# vldp-hw-rev03.net
KiCad netlist of a schematic drawn in EAGLE
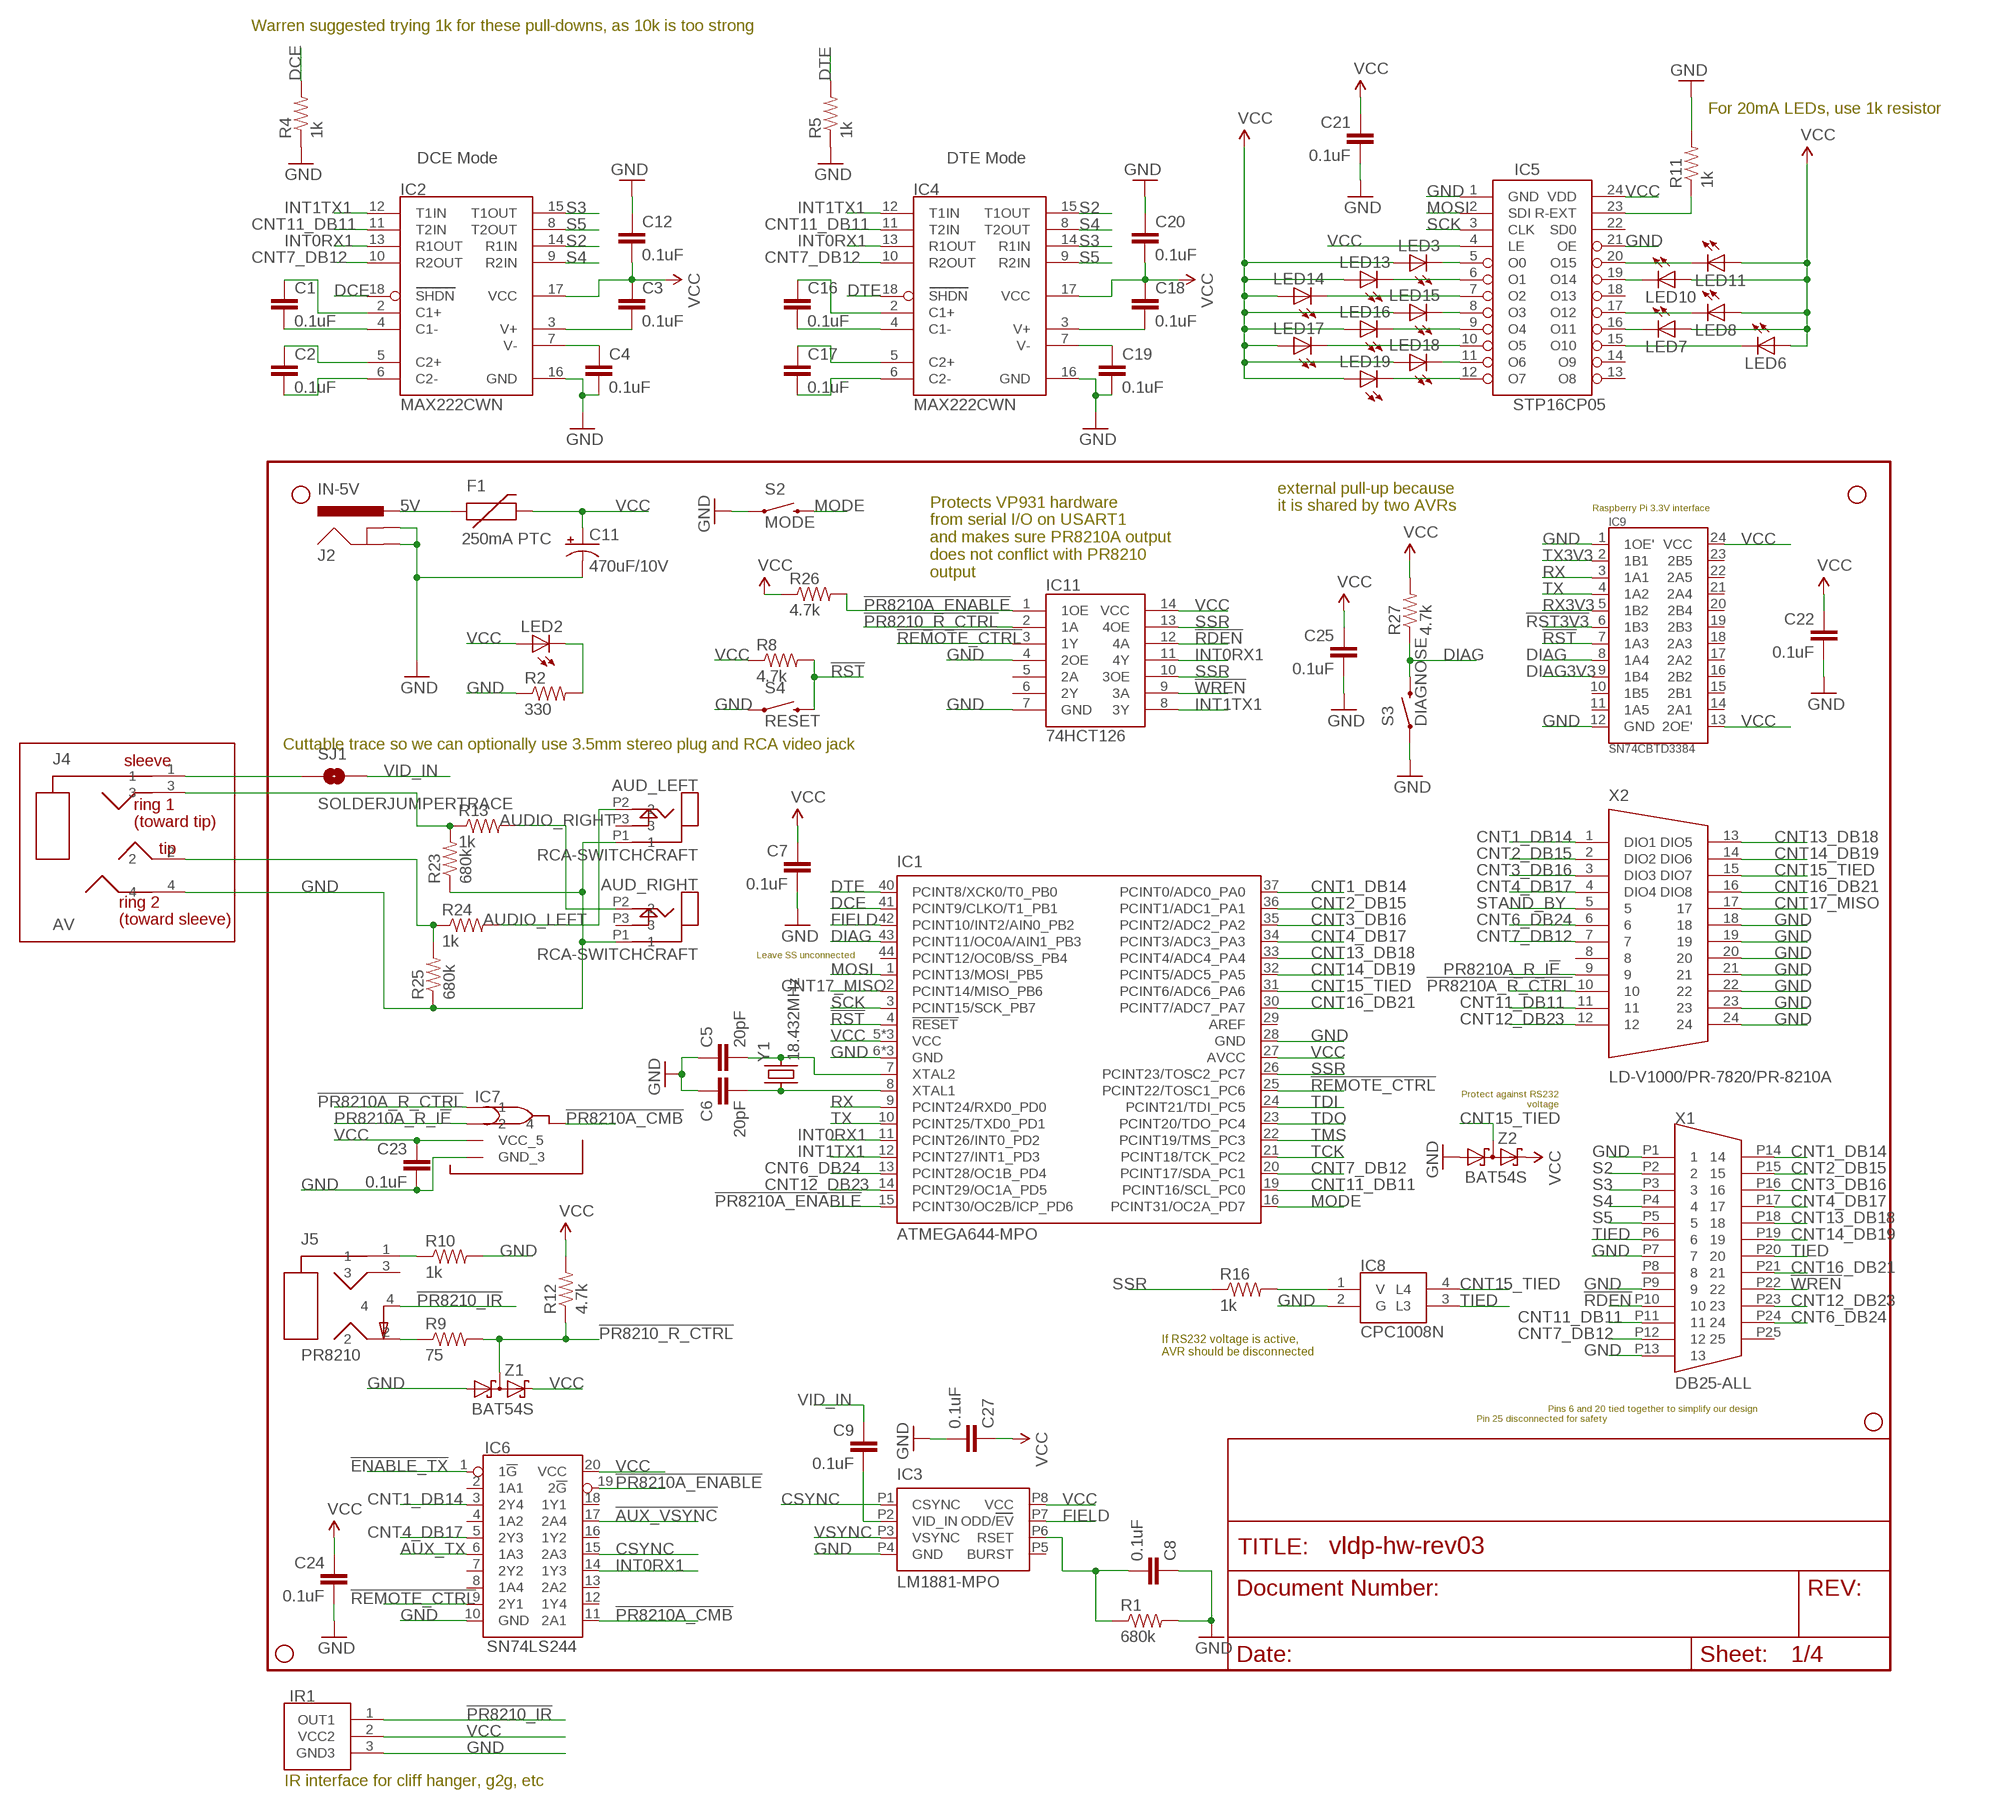
[diagram p0: schematic, sheet 1]
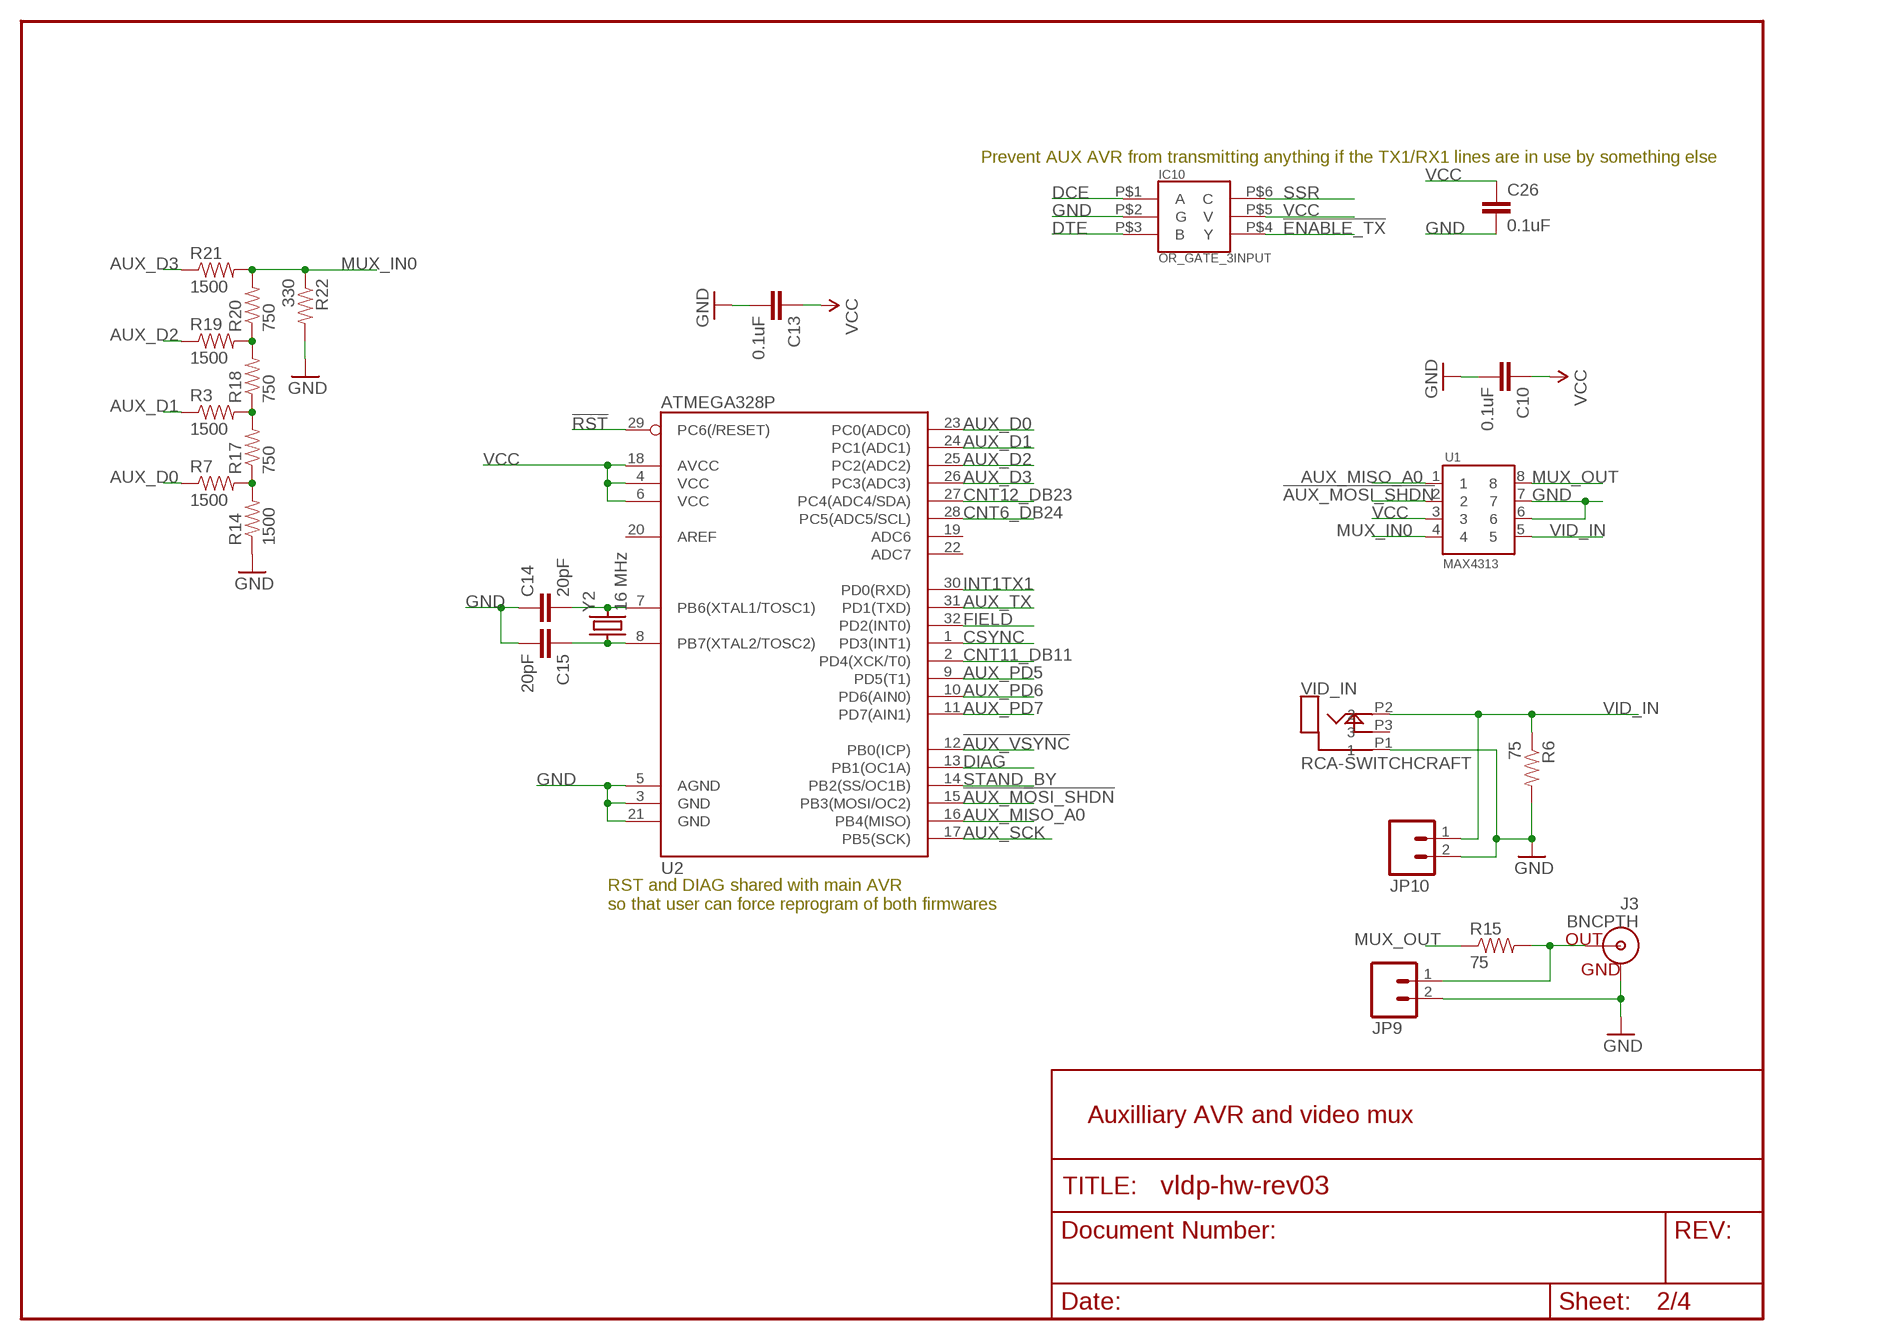
[diagram p1: schematic, sheet 2]
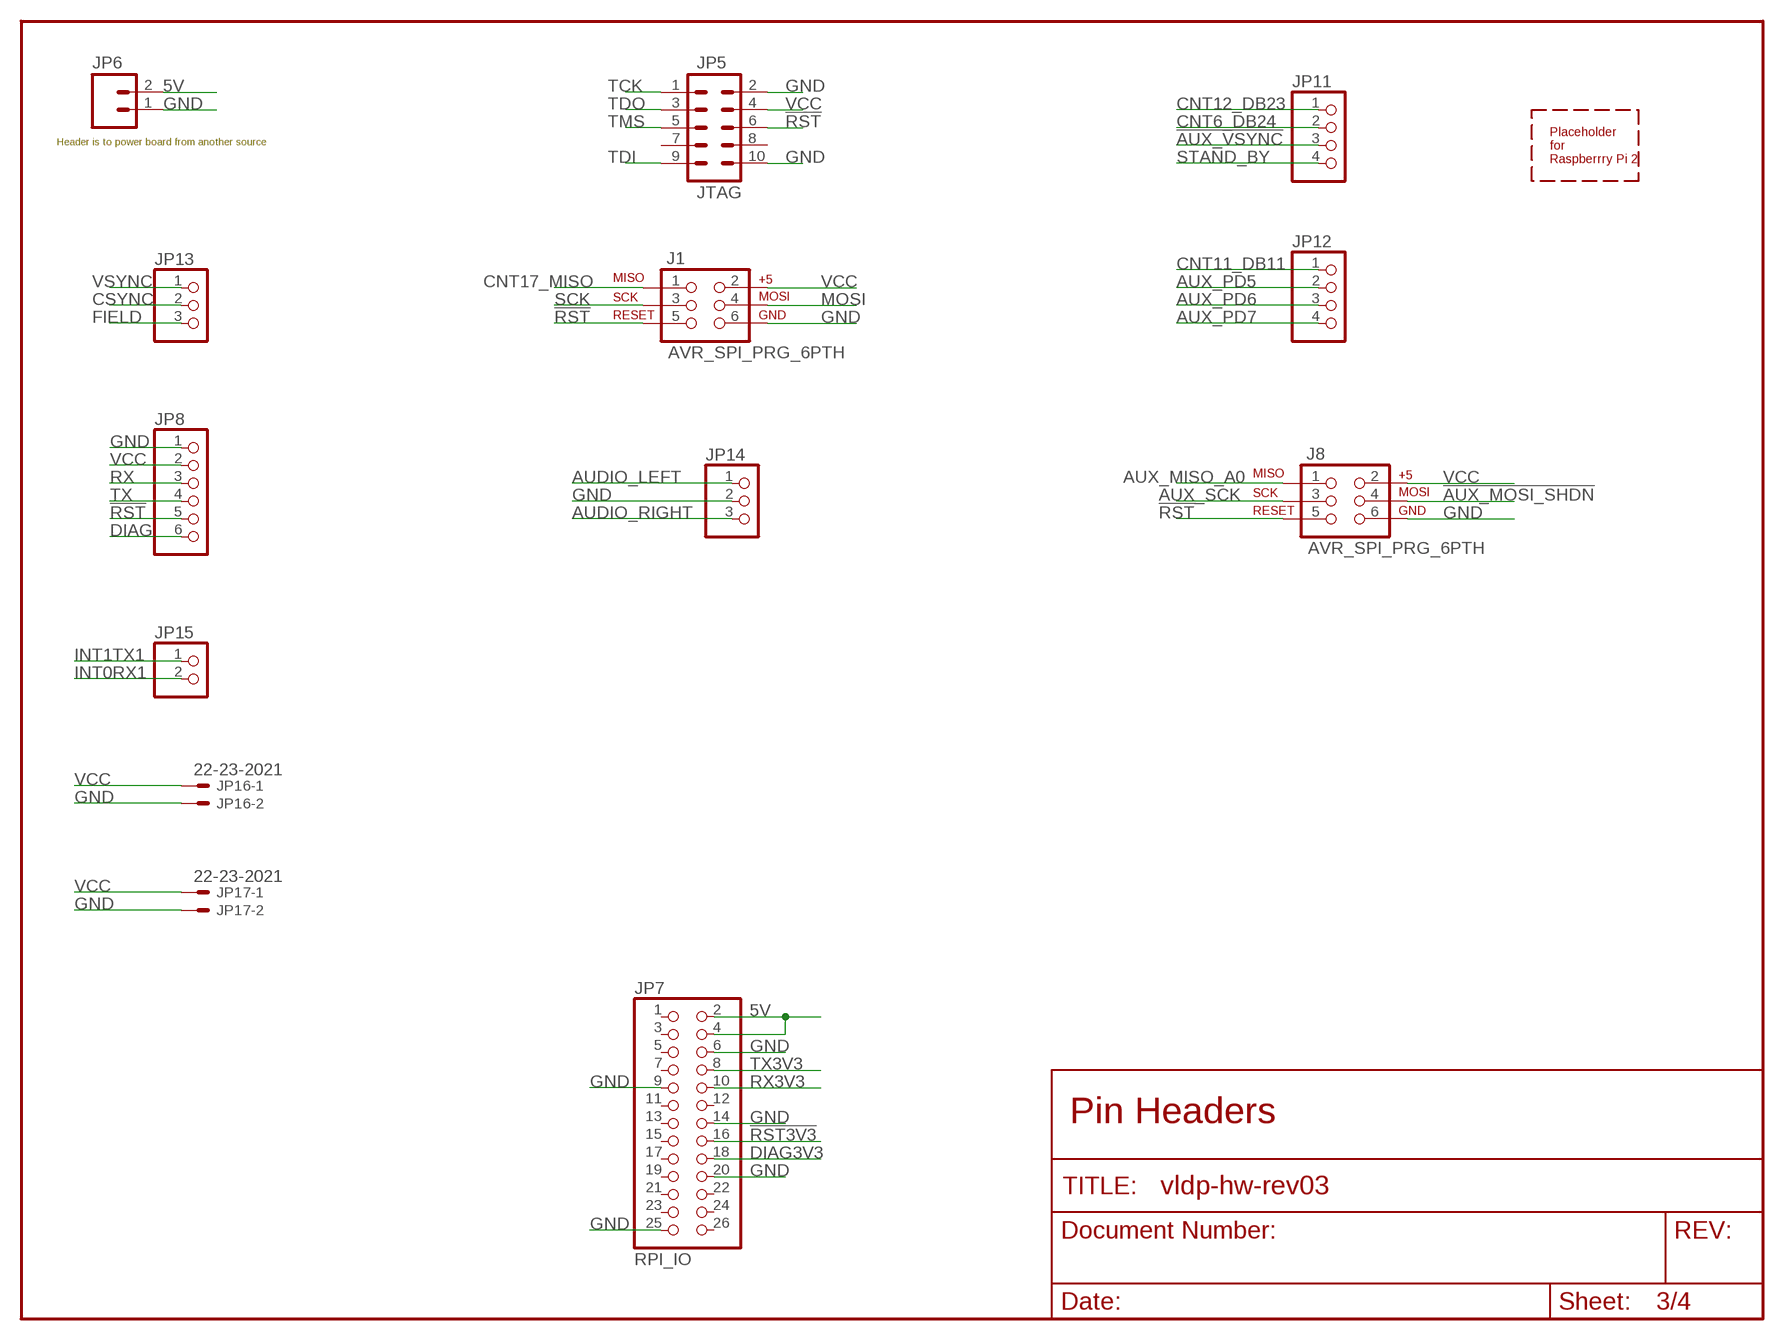
[diagram p2: schematic, sheet 3]

(export (version "E")
  (design (tool "Eeschema 10.0.6"))
  (components
    (comp (ref "J1")
      (value "AVR_SPI_PRG_6PTH")
      (footprint "eagle-import:2X3")
      (libsource (lib "eagle-import") (part "AVR_SPI_PRG_6PTH"))
    )
    (comp (ref "J8")
      (value "AVR_SPI_PRG_6PTH")
      (footprint "eagle-import:2X3")
      (libsource (lib "eagle-import") (part "AVR_SPI_PRG_6PTH"))
    )
    (comp (ref "JP5")
      (value "JTAG")
      (footprint "eagle-import:AVR_ICSP")
      (libsource (lib "eagle-import") (part "M05X2PTH"))
    )
    (comp (ref "JP6")
      (value "M02PTH")
      (footprint "eagle-import:1X02")
      (libsource (lib "eagle-import") (part "M02PTH"))
    )
    (comp (ref "JP7")
      (value "RPI_IO")
      (footprint "eagle-import:2X13")
      (libsource (lib "eagle-import") (part "PINHD-2X13"))
    )
    (comp (ref "JP8")
      (value "PINHD-1X6")
      (footprint "eagle-import:1X06")
      (libsource (lib "eagle-import") (part "PINHD-1X6"))
    )
    (comp (ref "JP11")
      (value "PINHD-1X4")
      (footprint "eagle-import:1X04")
      (libsource (lib "eagle-import") (part "PINHD-1X4"))
    )
    (comp (ref "JP12")
      (value "PINHD-1X4")
      (footprint "eagle-import:1X04")
      (libsource (lib "eagle-import") (part "PINHD-1X4"))
    )
    (comp (ref "JP13")
      (value "PINHD-1X3")
      (footprint "eagle-import:1X03")
      (libsource (lib "eagle-import") (part "PINHD-1X3"))
    )
    (comp (ref "JP14")
      (value "PINHD-1X3")
      (footprint "eagle-import:1X03")
      (libsource (lib "eagle-import") (part "PINHD-1X3"))
    )
    (comp (ref "JP15")
      (value "PINHD-1X2")
      (footprint "eagle-import:1X02")
      (libsource (lib "eagle-import") (part "PINHD-1X2"))
    )
    (comp (ref "JP16")
      (value "22-23-2021")
      (footprint "eagle-import:22-23-2021")
      (fields (field (name "MF") "MOLEX"))
      (libsource (lib "eagle-import") (part "22-23-2021"))
    )
    (comp (ref "JP17")
      (value "22-23-2021")
      (footprint "eagle-import:22-23-2021")
      (fields (field (name "MF") "MOLEX"))
      (libsource (lib "eagle-import") (part "22-23-2021"))
    )
    (comp (ref "U$1")
      (value "RASPBERRY_PI2_LAYOUT")
      (footprint "eagle-import:RPI2")
      (libsource (lib "eagle-import") (part "RASPBERRY_PI2_LAYOUT"))
    )
    (comp (ref "C10")
      (value "0.1uF")
      (footprint "eagle-import:1206")
      (libsource (lib "eagle-import") (part "CAP1206"))
    )
    (comp (ref "C13")
      (value "0.1uF")
      (footprint "eagle-import:1206")
      (libsource (lib "eagle-import") (part "CAP1206"))
    )
    (comp (ref "C14")
      (value "20pF")
      (footprint "eagle-import:1206")
      (libsource (lib "eagle-import") (part "CAP1206"))
    )
    (comp (ref "C15")
      (value "20pF")
      (footprint "eagle-import:1206")
      (libsource (lib "eagle-import") (part "CAP1206"))
    )
    (comp (ref "C26")
      (value "0.1uF")
      (footprint "eagle-import:1206")
      (libsource (lib "eagle-import") (part "CAP1206"))
    )
    (comp (ref "IC10")
      (value "OR_GATE_3INPUT")
      (footprint "eagle-import:TSSOP6-DCK")
      (libsource (lib "eagle-import") (part "OR_GATE_3INPUT"))
    )
    (comp (ref "J3")
      (value "BNCPTH")
      (footprint "eagle-import:BNC")
      (libsource (lib "eagle-import") (part "BNCPTH"))
    )
    (comp (ref "JP9")
      (value "M02PTH")
      (footprint "eagle-import:1X02")
      (libsource (lib "eagle-import") (part "M02PTH"))
    )
    (comp (ref "JP10")
      (value "M02PTH")
      (footprint "eagle-import:1X02")
      (libsource (lib "eagle-import") (part "M02PTH"))
    )
    (comp (ref "R3")
      (value "1500")
      (footprint "eagle-import:1206")
      (libsource (lib "eagle-import") (part "RESISTOR1206"))
    )
    (comp (ref "R6")
      (value "75")
      (footprint "eagle-import:1206")
      (libsource (lib "eagle-import") (part "RESISTOR1206"))
    )
    (comp (ref "R7")
      (value "1500")
      (footprint "eagle-import:1206")
      (libsource (lib "eagle-import") (part "RESISTOR1206"))
    )
    (comp (ref "R14")
      (value "1500")
      (footprint "eagle-import:1206")
      (libsource (lib "eagle-import") (part "RESISTOR1206"))
    )
    (comp (ref "R15")
      (value "75")
      (footprint "eagle-import:1206")
      (libsource (lib "eagle-import") (part "RESISTOR1206"))
    )
    (comp (ref "R17")
      (value "750")
      (footprint "eagle-import:1206")
      (libsource (lib "eagle-import") (part "RESISTOR1206"))
    )
    (comp (ref "R18")
      (value "750")
      (footprint "eagle-import:1206")
      (libsource (lib "eagle-import") (part "RESISTOR1206"))
    )
    (comp (ref "R19")
      (value "1500")
      (footprint "eagle-import:1206")
      (libsource (lib "eagle-import") (part "RESISTOR1206"))
    )
    (comp (ref "R20")
      (value "750")
      (footprint "eagle-import:1206")
      (libsource (lib "eagle-import") (part "RESISTOR1206"))
    )
    (comp (ref "R21")
      (value "1500")
      (footprint "eagle-import:1206")
      (libsource (lib "eagle-import") (part "RESISTOR1206"))
    )
    (comp (ref "R22")
      (value "330")
      (footprint "eagle-import:1206")
      (libsource (lib "eagle-import") (part "RESISTOR1206"))
    )
    (comp (ref "U1")
      (value "MAX4313")
      (footprint "eagle-import:MAXIM-UMAX-LONGPADS")
      (libsource (lib "eagle-import") (part "MAX4313UMAX"))
    )
    (comp (ref "U2")
      (value "ATMEGA328P")
      (footprint "eagle-import:TQFP32-LONGPADS")
      (libsource (lib "eagle-import") (part "ATMEGA168"))
    )
    (comp (ref "VID_IN")
      (value "RCA-SWITCHCRAFT")
      (footprint "eagle-import:RCA-SWITCHCRAFT-4X")
      (libsource (lib "eagle-import") (part "RCA-SWITCHCRAFT"))
    )
    (comp (ref "Y2")
      (value "16 MHz")
      (footprint "eagle-import:CRYSTAL-CSM-3X")
      (libsource (lib "eagle-import") (part "CRYSTAL"))
    )
    (comp (ref "AUD_LEFT")
      (value "RCA-SWITCHCRAFT")
      (footprint "eagle-import:RCA-SWITCHCRAFT-4X")
      (libsource (lib "eagle-import") (part "RCA-SWITCHCRAFT"))
    )
    (comp (ref "AUD_RIGHT")
      (value "RCA-SWITCHCRAFT")
      (footprint "eagle-import:RCA-SWITCHCRAFT-4X")
      (libsource (lib "eagle-import") (part "RCA-SWITCHCRAFT"))
    )
    (comp (ref "C1")
      (value "0.1uF")
      (footprint "eagle-import:1206")
      (libsource (lib "eagle-import") (part "CAP1206"))
    )
    (comp (ref "C2")
      (value "0.1uF")
      (footprint "eagle-import:1206")
      (libsource (lib "eagle-import") (part "CAP1206"))
    )
    (comp (ref "C3")
      (value "0.1uF")
      (footprint "eagle-import:1206")
      (libsource (lib "eagle-import") (part "CAP1206"))
    )
    (comp (ref "C4")
      (value "0.1uF")
      (footprint "eagle-import:1206")
      (libsource (lib "eagle-import") (part "CAP1206"))
    )
    (comp (ref "C5")
      (value "20pF")
      (footprint "eagle-import:1206")
      (libsource (lib "eagle-import") (part "CAP1206"))
    )
    (comp (ref "C6")
      (value "20pF")
      (footprint "eagle-import:1206")
      (libsource (lib "eagle-import") (part "CAP1206"))
    )
    (comp (ref "C7")
      (value "0.1uF")
      (footprint "eagle-import:1206")
      (libsource (lib "eagle-import") (part "CAP1206"))
    )
    (comp (ref "C8")
      (value "0.1uF")
      (footprint "eagle-import:1206")
      (libsource (lib "eagle-import") (part "CAP1206"))
    )
    (comp (ref "C9")
      (value "0.1uF")
      (footprint "eagle-import:1206")
      (libsource (lib "eagle-import") (part "CAP1206"))
    )
    (comp (ref "C11")
      (value "470uF/10V")
      (footprint "eagle-import:CPOL-RADIAL-10UF-25V")
      (libsource (lib "eagle-import") (part "CAP_POLPTH2"))
    )
    (comp (ref "C12")
      (value "0.1uF")
      (footprint "eagle-import:1206")
      (libsource (lib "eagle-import") (part "CAP1206"))
    )
    (comp (ref "C16")
      (value "0.1uF")
      (footprint "eagle-import:1206")
      (libsource (lib "eagle-import") (part "CAP1206"))
    )
    (comp (ref "C17")
      (value "0.1uF")
      (footprint "eagle-import:1206")
      (libsource (lib "eagle-import") (part "CAP1206"))
    )
    (comp (ref "C18")
      (value "0.1uF")
      (footprint "eagle-import:1206")
      (libsource (lib "eagle-import") (part "CAP1206"))
    )
    (comp (ref "C19")
      (value "0.1uF")
      (footprint "eagle-import:1206")
      (libsource (lib "eagle-import") (part "CAP1206"))
    )
    (comp (ref "C20")
      (value "0.1uF")
      (footprint "eagle-import:1206")
      (libsource (lib "eagle-import") (part "CAP1206"))
    )
    (comp (ref "C21")
      (value "0.1uF")
      (footprint "eagle-import:1206")
      (libsource (lib "eagle-import") (part "CAP1206"))
    )
    (comp (ref "C22")
      (value "0.1uF")
      (footprint "eagle-import:1206")
      (libsource (lib "eagle-import") (part "CAP1206"))
    )
    (comp (ref "C23")
      (value "0.1uF")
      (footprint "eagle-import:1206")
      (libsource (lib "eagle-import") (part "CAP1206"))
    )
    (comp (ref "C24")
      (value "0.1uF")
      (footprint "eagle-import:1206")
      (libsource (lib "eagle-import") (part "CAP1206"))
    )
    (comp (ref "C25")
      (value "0.1uF")
      (footprint "eagle-import:1206")
      (libsource (lib "eagle-import") (part "CAP1206"))
    )
    (comp (ref "C27")
      (value "0.1uF")
      (footprint "eagle-import:1206")
      (libsource (lib "eagle-import") (part "CAP1206"))
    )
    (comp (ref "F1")
      (value "250mA PTC")
      (footprint "eagle-import:PTC")
      (libsource (lib "eagle-import") (part "PTCPTH"))
    )
    (comp (ref "IC1")
      (value "ATMEGA644-MPO")
      (footprint "eagle-import:TQFP44")
      (libsource (lib "eagle-import") (part "ATMEGA644-MPO"))
    )
    (comp (ref "IC2")
      (value "MAX222CWN")
      (footprint "eagle-import:SO18")
      (libsource (lib "eagle-import") (part "MAX222CWN"))
    )
    (comp (ref "IC3")
      (value "LM1881-MPO")
      (footprint "eagle-import:LM1881M")
      (libsource (lib "eagle-import") (part "LM1881-MPO"))
    )
    (comp (ref "IC4")
      (value "MAX222CWN")
      (footprint "eagle-import:SO18")
      (libsource (lib "eagle-import") (part "MAX222CWN"))
    )
    (comp (ref "IC5")
      (value "STP16CP05")
      (footprint "eagle-import:TSSOP24")
      (libsource (lib "eagle-import") (part "STP16CP05TSSOP24"))
    )
    (comp (ref "IC6")
      (value "SN74LS244")
      (footprint "eagle-import:TSSOP20-MPO")
      (libsource (lib "eagle-import") (part "SN74LS244"))
    )
    (comp (ref "IC7")
      (value "PR8210A_RMT")
      (footprint "eagle-import:TSSOP5")
      (libsource (lib "eagle-import") (part "OR_GATE_2INPUT"))
    )
    (comp (ref "IC8")
      (value "CPC1008N")
      (footprint "eagle-import:CPC1008N")
      (libsource (lib "eagle-import") (part "CPC1008N"))
    )
    (comp (ref "IC9")
      (value "SN74CBTD3384")
      (footprint "eagle-import:TSSOP24")
      (libsource (lib "eagle-import") (part "SN74CBTD3384"))
    )
    (comp (ref "IC11")
      (value "74HCT126")
      (footprint "eagle-import:TSSOP14-MPO")
      (libsource (lib "eagle-import") (part "74HCT126"))
    )
    (comp (ref "IR1")
      (value "TSOP2438")
      (footprint "eagle-import:VISHAY")
      (libsource (lib "eagle-import") (part "TSOP2438"))
    )
    (comp (ref "J2")
      (value "IN-5V")
      (footprint "eagle-import:POWER_JACK_PTH")
      (libsource (lib "eagle-import") (part "POWER_JACKPTH"))
    )
    (comp (ref "J4")
      (value "AV")
      (footprint "eagle-import:3.5MM-SJ-43514")
      (libsource (lib "eagle-import") (part "3.5MM-4-TERMINALS"))
    )
    (comp (ref "J5")
      (value "PR8210")
      (footprint "eagle-import:3.5MM-SJ1-3554NG")
      (libsource (lib "eagle-import") (part "3.5MM-STEREO-WITH-TIP-SWITCH"))
    )
    (comp (ref "JP1")
      (value "STAND-OFF")
      (footprint "eagle-import:STAND-OFF")
      (libsource (lib "eagle-import") (part "STAND-OFF"))
    )
    (comp (ref "JP2")
      (value "STAND-OFF")
      (footprint "eagle-import:STAND-OFF")
      (libsource (lib "eagle-import") (part "STAND-OFF"))
    )
    (comp (ref "JP3")
      (value "STAND-OFF")
      (footprint "eagle-import:STAND-OFF")
      (libsource (lib "eagle-import") (part "STAND-OFF"))
    )
    (comp (ref "JP4")
      (value "STAND-OFF")
      (footprint "eagle-import:STAND-OFF")
      (libsource (lib "eagle-import") (part "STAND-OFF"))
    )
    (comp (ref "LED2")
      (value "LED1206")
      (footprint "eagle-import:LED-1206")
      (libsource (lib "eagle-import") (part "LED1206"))
    )
    (comp (ref "LED3")
      (value "LED1206")
      (footprint "eagle-import:LED-1206")
      (libsource (lib "eagle-import") (part "LED1206"))
    )
    (comp (ref "LED6")
      (value "LED1206")
      (footprint "eagle-import:LED-1206")
      (libsource (lib "eagle-import") (part "LED1206"))
    )
    (comp (ref "LED7")
      (value "LED1206")
      (footprint "eagle-import:LED-1206")
      (libsource (lib "eagle-import") (part "LED1206"))
    )
    (comp (ref "LED8")
      (value "LED1206")
      (footprint "eagle-import:LED-1206")
      (libsource (lib "eagle-import") (part "LED1206"))
    )
    (comp (ref "LED10")
      (value "LED1206")
      (footprint "eagle-import:LED-1206")
      (libsource (lib "eagle-import") (part "LED1206"))
    )
    (comp (ref "LED11")
      (value "LED1206")
      (footprint "eagle-import:LED-1206")
      (libsource (lib "eagle-import") (part "LED1206"))
    )
    (comp (ref "LED13")
      (value "LED1206")
      (footprint "eagle-import:LED-1206")
      (libsource (lib "eagle-import") (part "LED1206"))
    )
    (comp (ref "LED14")
      (value "LED1206")
      (footprint "eagle-import:LED-1206")
      (libsource (lib "eagle-import") (part "LED1206"))
    )
    (comp (ref "LED15")
      (value "LED1206")
      (footprint "eagle-import:LED-1206")
      (libsource (lib "eagle-import") (part "LED1206"))
    )
    (comp (ref "LED16")
      (value "LED1206")
      (footprint "eagle-import:LED-1206")
      (libsource (lib "eagle-import") (part "LED1206"))
    )
    (comp (ref "LED17")
      (value "LED1206")
      (footprint "eagle-import:LED-1206")
      (libsource (lib "eagle-import") (part "LED1206"))
    )
    (comp (ref "LED18")
      (value "LED1206")
      (footprint "eagle-import:LED-1206")
      (libsource (lib "eagle-import") (part "LED1206"))
    )
    (comp (ref "LED19")
      (value "LED1206")
      (footprint "eagle-import:LED-1206")
      (libsource (lib "eagle-import") (part "LED1206"))
    )
    (comp (ref "R1")
      (value "680k")
      (footprint "eagle-import:1206")
      (libsource (lib "eagle-import") (part "RESISTOR1206"))
    )
    (comp (ref "R2")
      (value "330")
      (footprint "eagle-import:1206")
      (libsource (lib "eagle-import") (part "RESISTOR1206"))
    )
    (comp (ref "R4")
      (value "1k")
      (footprint "eagle-import:1206")
      (libsource (lib "eagle-import") (part "RESISTOR1206"))
    )
    (comp (ref "R5")
      (value "1k")
      (footprint "eagle-import:1206")
      (libsource (lib "eagle-import") (part "RESISTOR1206"))
    )
    (comp (ref "R8")
      (value "4.7k")
      (footprint "eagle-import:1206")
      (libsource (lib "eagle-import") (part "RESISTOR1206"))
    )
    (comp (ref "R9")
      (value "75")
      (footprint "eagle-import:1206")
      (libsource (lib "eagle-import") (part "RESISTOR1206"))
    )
    (comp (ref "R10")
      (value "1k")
      (footprint "eagle-import:1206")
      (libsource (lib "eagle-import") (part "RESISTOR1206"))
    )
    (comp (ref "R11")
      (value "1k")
      (footprint "eagle-import:1206")
      (libsource (lib "eagle-import") (part "RESISTOR1206"))
    )
    (comp (ref "R12")
      (value "4.7k")
      (footprint "eagle-import:1206")
      (libsource (lib "eagle-import") (part "RESISTOR1206"))
    )
    (comp (ref "R13")
      (value "1k")
      (footprint "eagle-import:1206")
      (libsource (lib "eagle-import") (part "RESISTOR1206"))
    )
    (comp (ref "R16")
      (value "1k")
      (footprint "eagle-import:1206")
      (libsource (lib "eagle-import") (part "RESISTOR1206"))
    )
    (comp (ref "R23")
      (value "680k")
      (footprint "eagle-import:1206")
      (libsource (lib "eagle-import") (part "RESISTOR1206"))
    )
    (comp (ref "R24")
      (value "1k")
      (footprint "eagle-import:1206")
      (libsource (lib "eagle-import") (part "RESISTOR1206"))
    )
    (comp (ref "R25")
      (value "680k")
      (footprint "eagle-import:1206")
      (libsource (lib "eagle-import") (part "RESISTOR1206"))
    )
    (comp (ref "R26")
      (value "4.7k")
      (footprint "eagle-import:1206")
      (libsource (lib "eagle-import") (part "RESISTOR1206"))
    )
    (comp (ref "R27")
      (value "4.7k")
      (footprint "eagle-import:1206")
      (libsource (lib "eagle-import") (part "RESISTOR1206"))
    )
    (comp (ref "S2")
      (value "MODE")
      (footprint "eagle-import:TACTILE-PTH")
      (libsource (lib "eagle-import") (part "SWITCH-MOMENTARY-2PTH"))
    )
    (comp (ref "S3")
      (value "DIAGNOSE")
      (footprint "eagle-import:TACTILE-PTH")
      (libsource (lib "eagle-import") (part "SWITCH-MOMENTARY-2PTH"))
    )
    (comp (ref "S4")
      (value "RESET")
      (footprint "eagle-import:TACTILE-PTH")
      (libsource (lib "eagle-import") (part "SWITCH-MOMENTARY-2PTH"))
    )
    (comp (ref "SJ1")
      (value "SOLDERJUMPERTRACE")
      (footprint "eagle-import:SJ_2S-TRACE")
      (libsource (lib "eagle-import") (part "SOLDERJUMPERTRACE"))
    )
    (comp (ref "X1")
      (value "DB25-ALL")
      (footprint "eagle-import:A32077-ND")
      (libsource (lib "eagle-import") (part "A32077-ND"))
    )
    (comp (ref "X2")
      (value "LD-V1000/PR-7820/PR-8210A")
      (footprint "eagle-import:112-YYY-213R001")
      (libsource (lib "eagle-import") (part "111-024-213L001RIGHTANGLE"))
    )
    (comp (ref "Y1")
      (value "18.432MHz")
      (footprint "eagle-import:CRYSTAL-CSM-3X")
      (libsource (lib "eagle-import") (part "CRYSTAL"))
    )
    (comp (ref "Z1")
      (value "BAT54S")
      (footprint "eagle-import:SOT23")
      (libsource (lib "eagle-import") (part "BAT54S"))
    )
    (comp (ref "Z2")
      (value "BAT54S")
      (footprint "eagle-import:SOT23")
      (libsource (lib "eagle-import") (part "BAT54S"))
    )
  )
  (nets
    (net (code "1") (name "5V") (class "Default")
      (node (ref "F1") (pin "P$1") (pinfunction "1_P$1") (pintype "bidirectional"))
      (node (ref "J2") (pin "PWR") (pinfunction "PWR_PWR") (pintype "bidirectional"))
      (node (ref "JP6") (pin "2") (pinfunction "2_2") (pintype "passive"))
      (node (ref "JP7") (pin "2") (pinfunction "2_2") (pintype "passive"))
      (node (ref "JP7") (pin "4") (pinfunction "4_4") (pintype "passive"))
    )
    (net (code "2") (name "AUDIO_LEFT") (class "Default")
      (node (ref "AUD_LEFT") (pin "P2") (pinfunction "2_P2") (pintype "bidirectional"))
      (node (ref "JP14") (pin "1") (pinfunction "1_1") (pintype "passive"))
      (node (ref "R24") (pin "2") (pinfunction "2_2") (pintype "passive"))
    )
    (net (code "3") (name "AUDIO_RIGHT") (class "Default")
      (node (ref "AUD_RIGHT") (pin "P2") (pinfunction "2_P2") (pintype "bidirectional"))
      (node (ref "JP14") (pin "3") (pinfunction "3_3") (pintype "passive"))
      (node (ref "R13") (pin "2") (pinfunction "2_2") (pintype "passive"))
    )
    (net (code "4") (name "AUX_D0") (class "Default")
      (node (ref "R7") (pin "1") (pinfunction "1_1") (pintype "passive"))
      (node (ref "U2") (pin "23") (pinfunction "PC0(ADC0)_23") (pintype "bidirectional"))
    )
    (net (code "5") (name "AUX_D1") (class "Default")
      (node (ref "R3") (pin "1") (pinfunction "1_1") (pintype "passive"))
      (node (ref "U2") (pin "24") (pinfunction "PC1(ADC1)_24") (pintype "bidirectional"))
    )
    (net (code "6") (name "AUX_D2") (class "Default")
      (node (ref "R19") (pin "1") (pinfunction "1_1") (pintype "passive"))
      (node (ref "U2") (pin "25") (pinfunction "PC2(ADC2)_25") (pintype "bidirectional"))
    )
    (net (code "7") (name "AUX_D3") (class "Default")
      (node (ref "R21") (pin "1") (pinfunction "1_1") (pintype "passive"))
      (node (ref "U2") (pin "26") (pinfunction "PC3(ADC3)_26") (pintype "bidirectional"))
    )
    (net (code "8") (name "AUX_MISO_A0") (class "Default")
      (node (ref "J8") (pin "1") (pinfunction "1_1") (pintype "passive"))
      (node (ref "U1") (pin "1") (pinfunction "1_1") (pintype "bidirectional"))
      (node (ref "U2") (pin "16") (pinfunction "PB4(MISO)_16") (pintype "bidirectional"))
    )
    (net (code "9") (name "AUX_PD5") (class "Default")
      (node (ref "JP12") (pin "2") (pinfunction "2_2") (pintype "passive"))
      (node (ref "U2") (pin "9") (pinfunction "PD5(T1)_9") (pintype "bidirectional"))
    )
    (net (code "10") (name "AUX_PD6") (class "Default")
      (node (ref "JP12") (pin "3") (pinfunction "3_3") (pintype "passive"))
      (node (ref "U2") (pin "10") (pinfunction "PD6(AIN0)_10") (pintype "bidirectional"))
    )
    (net (code "11") (name "AUX_PD7") (class "Default")
      (node (ref "JP12") (pin "4") (pinfunction "4_4") (pintype "passive"))
      (node (ref "U2") (pin "11") (pinfunction "PD7(AIN1)_11") (pintype "bidirectional"))
    )
    (net (code "12") (name "AUX_SCK") (class "Default")
      (node (ref "J8") (pin "3") (pinfunction "3_3") (pintype "passive"))
      (node (ref "U2") (pin "17") (pinfunction "PB5(SCK)_17") (pintype "bidirectional"))
    )
    (net (code "13") (name "AUX_TX") (class "Default")
      (node (ref "IC6") (pin "6") (pinfunction "1A3_6") (pintype "bidirectional"))
      (node (ref "U2") (pin "31") (pinfunction "PD1(TXD)_31") (pintype "bidirectional"))
    )
    (net (code "14") (name "CNT1_DB14") (class "Default")
      (node (ref "IC1") (pin "37") (pinfunction "PCINT0/ADC0_PA0_37") (pintype "bidirectional"))
      (node (ref "IC6") (pin "3") (pinfunction "2Y4_3") (pintype "bidirectional"))
      (node (ref "X1") (pin "P14") (pinfunction "14_P14") (pintype "bidirectional"))
      (node (ref "X2") (pin "1") (pinfunction "DIO1_1") (pintype "bidirectional"))
    )
    (net (code "15") (name "CNT2_DB15") (class "Default")
      (node (ref "IC1") (pin "36") (pinfunction "PCINT1/ADC1_PA1_36") (pintype "bidirectional"))
      (node (ref "X1") (pin "P15") (pinfunction "15_P15") (pintype "bidirectional"))
      (node (ref "X2") (pin "2") (pinfunction "DIO2_2") (pintype "bidirectional"))
    )
    (net (code "16") (name "CNT3_DB16") (class "Default")
      (node (ref "IC1") (pin "35") (pinfunction "PCINT2/ADC2_PA2_35") (pintype "bidirectional"))
      (node (ref "X1") (pin "P16") (pinfunction "16_P16") (pintype "bidirectional"))
      (node (ref "X2") (pin "3") (pinfunction "DIO3_3") (pintype "bidirectional"))
    )
    (net (code "17") (name "CNT4_DB17") (class "Default")
      (node (ref "IC1") (pin "34") (pinfunction "PCINT3/ADC3_PA3_34") (pintype "bidirectional"))
      (node (ref "IC6") (pin "5") (pinfunction "2Y3_5") (pintype "bidirectional"))
      (node (ref "X1") (pin "P17") (pinfunction "17_P17") (pintype "bidirectional"))
      (node (ref "X2") (pin "4") (pinfunction "DIO4_4") (pintype "bidirectional"))
    )
    (net (code "18") (name "CNT6_DB24") (class "Default")
      (node (ref "IC1") (pin "13") (pinfunction "PCINT28/OC1B_PD4_13") (pintype "bidirectional"))
      (node (ref "JP11") (pin "2") (pinfunction "2_2") (pintype "passive"))
      (node (ref "U2") (pin "28") (pinfunction "PC5(ADC5/SCL)_28") (pintype "bidirectional"))
      (node (ref "X1") (pin "P24") (pinfunction "24_P24") (pintype "bidirectional"))
      (node (ref "X2") (pin "6") (pinfunction "6_6") (pintype "bidirectional"))
    )
    (net (code "19") (name "CNT7_DB12") (class "Default")
      (node (ref "IC1") (pin "20") (pinfunction "PCINT17/SDA_PC1_20") (pintype "bidirectional"))
      (node (ref "IC2") (pin "10") (pinfunction "R2OUT_10") (pintype "output"))
      (node (ref "IC4") (pin "10") (pinfunction "R2OUT_10") (pintype "output"))
      (node (ref "X1") (pin "P12") (pinfunction "12_P12") (pintype "bidirectional"))
      (node (ref "X2") (pin "7") (pinfunction "7_7") (pintype "bidirectional"))
    )
    (net (code "20") (name "CNT11_DB11") (class "Default")
      (node (ref "IC1") (pin "19") (pinfunction "PCINT16/SCL_PC0_19") (pintype "bidirectional"))
      (node (ref "IC2") (pin "11") (pinfunction "T2IN_11") (pintype "input"))
      (node (ref "IC4") (pin "11") (pinfunction "T2IN_11") (pintype "input"))
      (node (ref "JP12") (pin "1") (pinfunction "1_1") (pintype "passive"))
      (node (ref "U2") (pin "2") (pinfunction "PD4(XCK/T0)_2") (pintype "bidirectional"))
      (node (ref "X1") (pin "P11") (pinfunction "11_P11") (pintype "bidirectional"))
      (node (ref "X2") (pin "11") (pinfunction "11_11") (pintype "bidirectional"))
    )
    (net (code "21") (name "CNT12_DB23") (class "Default")
      (node (ref "IC1") (pin "14") (pinfunction "PCINT29/OC1A_PD5_14") (pintype "bidirectional"))
      (node (ref "JP11") (pin "1") (pinfunction "1_1") (pintype "passive"))
      (node (ref "U2") (pin "27") (pinfunction "PC4(ADC4/SDA)_27") (pintype "bidirectional"))
      (node (ref "X1") (pin "P23") (pinfunction "23_P23") (pintype "bidirectional"))
      (node (ref "X2") (pin "12") (pinfunction "12_12") (pintype "bidirectional"))
    )
    (net (code "22") (name "CNT13_DB18") (class "Default")
      (node (ref "IC1") (pin "33") (pinfunction "PCINT4/ADC4_PA4_33") (pintype "bidirectional"))
      (node (ref "X1") (pin "P18") (pinfunction "18_P18") (pintype "bidirectional"))
      (node (ref "X2") (pin "13") (pinfunction "DIO5_13") (pintype "bidirectional"))
    )
    (net (code "23") (name "CNT14_DB19") (class "Default")
      (node (ref "IC1") (pin "32") (pinfunction "PCINT5/ADC5_PA5_32") (pintype "bidirectional"))
      (node (ref "X1") (pin "P19") (pinfunction "19_P19") (pintype "bidirectional"))
      (node (ref "X2") (pin "14") (pinfunction "DIO6_14") (pintype "bidirectional"))
    )
    (net (code "24") (name "CNT15_TIED") (class "Default")
      (node (ref "IC1") (pin "31") (pinfunction "PCINT6/ADC6_PA6_31") (pintype "bidirectional"))
      (node (ref "IC8") (pin "4") (pinfunction "L4_4") (pintype "bidirectional"))
      (node (ref "X2") (pin "15") (pinfunction "DIO7_15") (pintype "bidirectional"))
      (node (ref "Z2") (pin "3") (pinfunction "C1A2_3") (pintype "passive"))
    )
    (net (code "25") (name "CNT16_DB21") (class "Default")
      (node (ref "IC1") (pin "30") (pinfunction "PCINT7/ADC7_PA7_30") (pintype "bidirectional"))
      (node (ref "X1") (pin "P21") (pinfunction "21_P21") (pintype "bidirectional"))
      (node (ref "X2") (pin "16") (pinfunction "DIO8_16") (pintype "bidirectional"))
    )
    (net (code "26") (name "CNT17_MISO") (class "Default")
      (node (ref "IC1") (pin "2") (pinfunction "PCINT14/MISO_PB6_2") (pintype "bidirectional"))
      (node (ref "J1") (pin "1") (pinfunction "1_1") (pintype "passive"))
      (node (ref "X2") (pin "17") (pinfunction "17_17") (pintype "bidirectional"))
    )
    (net (code "27") (name "CSYNC") (class "Default")
      (node (ref "IC3") (pin "P1") (pinfunction "CSYNC_P1") (pintype "output"))
      (node (ref "IC6") (pin "15") (pinfunction "2A3_15") (pintype "bidirectional"))
      (node (ref "JP13") (pin "2") (pinfunction "2_2") (pintype "passive"))
      (node (ref "U2") (pin "1") (pinfunction "PD3(INT1)_1") (pintype "bidirectional"))
    )
    (net (code "28") (name "DCE") (class "Default")
      (node (ref "IC1") (pin "41") (pinfunction "PCINT9/CLKO/T1_PB1_41") (pintype "bidirectional"))
      (node (ref "IC10") (pin "P$1") (pinfunction "A_P$1") (pintype "bidirectional"))
      (node (ref "IC2") (pin "18") (pinfunction "SHDN_18") (pintype "input"))
      (node (ref "R4") (pin "2") (pinfunction "2_2") (pintype "passive"))
    )
    (net (code "29") (name "DIAG") (class "Default")
      (node (ref "IC1") (pin "43") (pinfunction "PCINT11/OC0A/AIN1_PB3_43") (pintype "bidirectional"))
      (node (ref "IC9") (pin "8") (pinfunction "1A4_8") (pintype "bidirectional"))
      (node (ref "JP8") (pin "6") (pinfunction "6_6") (pintype "passive"))
      (node (ref "R27") (pin "1") (pinfunction "1_1") (pintype "passive"))
      (node (ref "S3") (pin "3") (pinfunction "2_3") (pintype "passive"))
      (node (ref "U2") (pin "13") (pinfunction "PB1(OC1A)_13") (pintype "bidirectional"))
    )
    (net (code "30") (name "DIAG3V3") (class "Default")
      (node (ref "IC9") (pin "9") (pinfunction "1B4_9") (pintype "bidirectional"))
      (node (ref "JP7") (pin "18") (pinfunction "18_18") (pintype "passive"))
    )
    (net (code "31") (name "DTE") (class "Default")
      (node (ref "IC1") (pin "40") (pinfunction "PCINT8/XCK0/T0_PB0_40") (pintype "bidirectional"))
      (node (ref "IC10") (pin "P$3") (pinfunction "B_P$3") (pintype "bidirectional"))
      (node (ref "IC4") (pin "18") (pinfunction "SHDN_18") (pintype "input"))
      (node (ref "R5") (pin "2") (pinfunction "2_2") (pintype "passive"))
    )
    (net (code "32") (name "FIELD") (class "Default")
      (node (ref "IC1") (pin "42") (pinfunction "PCINT10/INT2/AIN0_PB2_42") (pintype "bidirectional"))
      (node (ref "IC3") (pin "P7") (pinfunction "ODD/EV_P7") (pintype "output"))
      (node (ref "JP13") (pin "3") (pinfunction "3_3") (pintype "passive"))
      (node (ref "U2") (pin "32") (pinfunction "PD2(INT0)_32") (pintype "bidirectional"))
    )
    (net (code "33") (name "GND") (class "Default")
      (node (ref "AUD_LEFT") (pin "P1") (pinfunction "1_P1") (pintype "bidirectional"))
      (node (ref "AUD_RIGHT") (pin "P1") (pinfunction "1_P1") (pintype "bidirectional"))
      (node (ref "C10") (pin "2") (pinfunction "2_2") (pintype "passive"))
      (node (ref "C11") (pin "2") (pinfunction "-_2") (pintype "passive"))
      (node (ref "C12") (pin "1") (pinfunction "1_1") (pintype "passive"))
      (node (ref "C13") (pin "2") (pinfunction "2_2") (pintype "passive"))
      (node (ref "C14") (pin "1") (pinfunction "1_1") (pintype "passive"))
      (node (ref "C15") (pin "2") (pinfunction "2_2") (pintype "passive"))
      (node (ref "C19") (pin "2") (pinfunction "2_2") (pintype "passive"))
      (node (ref "C20") (pin "1") (pinfunction "1_1") (pintype "passive"))
      (node (ref "C21") (pin "2") (pinfunction "2_2") (pintype "passive"))
      (node (ref "C22") (pin "2") (pinfunction "2_2") (pintype "passive"))
      (node (ref "C23") (pin "2") (pinfunction "2_2") (pintype "passive"))
      (node (ref "C24") (pin "2") (pinfunction "2_2") (pintype "passive"))
      (node (ref "C25") (pin "2") (pinfunction "2_2") (pintype "passive"))
      (node (ref "C26") (pin "2") (pinfunction "2_2") (pintype "passive"))
      (node (ref "C27") (pin "2") (pinfunction "2_2") (pintype "passive"))
      (node (ref "C4") (pin "2") (pinfunction "2_2") (pintype "passive"))
      (node (ref "C5") (pin "1") (pinfunction "1_1") (pintype "passive"))
      (node (ref "C6") (pin "1") (pinfunction "1_1") (pintype "passive"))
      (node (ref "C7") (pin "2") (pinfunction "2_2") (pintype "passive"))
      (node (ref "C8") (pin "1") (pinfunction "1_1") (pintype "passive"))
      (node (ref "IC1") (pin "18") (pinfunction "GND_18") (pintype "power_in"))
      (node (ref "IC1") (pin "28") (pinfunction "GND_28") (pintype "power_in"))
      (node (ref "IC1") (pin "39") (pinfunction "GND_39") (pintype "power_in"))
      (node (ref "IC1") (pin "6") (pinfunction "GND_6") (pintype "power_in"))
      (node (ref "IC10") (pin "P$2") (pinfunction "G_P$2") (pintype "bidirectional"))
      (node (ref "IC11") (pin "4") (pinfunction "2OE_4") (pintype "bidirectional"))
      (node (ref "IC11") (pin "7") (pinfunction "GND_7") (pintype "bidirectional"))
      (node (ref "IC2") (pin "16") (pinfunction "GND_16") (pintype "power_in"))
      (node (ref "IC3") (pin "P4") (pinfunction "GND_P4") (pintype "power_in"))
      (node (ref "IC4") (pin "16") (pinfunction "GND_16") (pintype "power_in"))
      (node (ref "IC5") (pin "1") (pinfunction "GND_1") (pintype "bidirectional"))
      (node (ref "IC5") (pin "21") (pinfunction "OE_21") (pintype "bidirectional"))
      (node (ref "IC6") (pin "10") (pinfunction "GND_10") (pintype "bidirectional"))
      (node (ref "IC7") (pin "P$3") (pinfunction "GND_3_P$3") (pintype "bidirectional"))
      (node (ref "IC8") (pin "2") (pinfunction "G_2") (pintype "bidirectional"))
      (node (ref "IC9") (pin "1") (pinfunction "1OE'_1") (pintype "bidirectional"))
      (node (ref "IC9") (pin "12") (pinfunction "GND_12") (pintype "bidirectional"))
      (node (ref "IR1") (pin "3") (pinfunction "GND3_3") (pintype "bidirectional"))
      (node (ref "J1") (pin "6") (pinfunction "6_6") (pintype "passive"))
      (node (ref "J2") (pin "GND") (pinfunction "GND_GND") (pintype "bidirectional"))
      (node (ref "J2") (pin "GNDBREAK") (pinfunction "GNDBREAK_GNDBREAK") (pintype "bidirectional"))
      (node (ref "J3") (pin "GND") (pinfunction "GND_GND") (pintype "bidirectional"))
      (node (ref "J4") (pin "4") (pinfunction "4_4") (pintype "bidirectional"))
      (node (ref "J8") (pin "6") (pinfunction "6_6") (pintype "passive"))
      (node (ref "JP10") (pin "2") (pinfunction "2_2") (pintype "passive"))
      (node (ref "JP14") (pin "2") (pinfunction "2_2") (pintype "passive"))
      (node (ref "JP16") (pin "2") (pinfunction "S_2") (pintype "passive"))
      (node (ref "JP17") (pin "2") (pinfunction "S_2") (pintype "passive"))
      (node (ref "JP5") (pin "10") (pinfunction "10_10") (pintype "passive"))
      (node (ref "JP5") (pin "2") (pinfunction "2_2") (pintype "passive"))
      (node (ref "JP6") (pin "1") (pinfunction "1_1") (pintype "passive"))
      (node (ref "JP7") (pin "14") (pinfunction "14_14") (pintype "passive"))
      (node (ref "JP7") (pin "20") (pinfunction "20_20") (pintype "passive"))
      (node (ref "JP7") (pin "25") (pinfunction "25_25") (pintype "passive"))
      (node (ref "JP7") (pin "6") (pinfunction "6_6") (pintype "passive"))
      (node (ref "JP7") (pin "9") (pinfunction "9_9") (pintype "passive"))
      (node (ref "JP8") (pin "1") (pinfunction "1_1") (pintype "passive"))
      (node (ref "JP9") (pin "2") (pinfunction "2_2") (pintype "passive"))
      (node (ref "R1") (pin "2") (pinfunction "2_2") (pintype "passive"))
      (node (ref "R10") (pin "2") (pinfunction "2_2") (pintype "passive"))
      (node (ref "R11") (pin "2") (pinfunction "2_2") (pintype "passive"))
      (node (ref "R14") (pin "1") (pinfunction "1_1") (pintype "passive"))
      (node (ref "R2") (pin "1") (pinfunction "1_1") (pintype "passive"))
      (node (ref "R22") (pin "2") (pinfunction "2_2") (pintype "passive"))
      (node (ref "R23") (pin "1") (pinfunction "1_1") (pintype "passive"))
      (node (ref "R25") (pin "1") (pinfunction "1_1") (pintype "passive"))
      (node (ref "R4") (pin "1") (pinfunction "1_1") (pintype "passive"))
      (node (ref "R5") (pin "1") (pinfunction "1_1") (pintype "passive"))
      (node (ref "R6") (pin "2") (pinfunction "2_2") (pintype "passive"))
      (node (ref "S2") (pin "1") (pinfunction "1_1") (pintype "passive"))
      (node (ref "S3") (pin "1") (pinfunction "1_1") (pintype "passive"))
      (node (ref "S4") (pin "1") (pinfunction "1_1") (pintype "passive"))
      (node (ref "U1") (pin "6") (pinfunction "6_6") (pintype "bidirectional"))
      (node (ref "U1") (pin "7") (pinfunction "7_7") (pintype "bidirectional"))
      (node (ref "U2") (pin "21") (pinfunction "GND_21") (pintype "bidirectional"))
      (node (ref "U2") (pin "3") (pinfunction "GND_3") (pintype "bidirectional"))
      (node (ref "U2") (pin "5") (pinfunction "AGND_5") (pintype "bidirectional"))
      (node (ref "VID_IN") (pin "P1") (pinfunction "1_P1") (pintype "bidirectional"))
      (node (ref "X1") (pin "P1") (pinfunction "1_P1") (pintype "bidirectional"))
      (node (ref "X1") (pin "P13") (pinfunction "13_P13") (pintype "bidirectional"))
      (node (ref "X1") (pin "P7") (pinfunction "7_P7") (pintype "bidirectional"))
      (node (ref "X1") (pin "P9") (pinfunction "9_P9") (pintype "bidirectional"))
      (node (ref "X2") (pin "18") (pinfunction "18_18") (pintype "bidirectional"))
      (node (ref "X2") (pin "19") (pinfunction "19_19") (pintype "bidirectional"))
      (node (ref "X2") (pin "20") (pinfunction "20_20") (pintype "bidirectional"))
      (node (ref "X2") (pin "21") (pinfunction "21_21") (pintype "bidirectional"))
      (node (ref "X2") (pin "22") (pinfunction "22_22") (pintype "bidirectional"))
      (node (ref "X2") (pin "23") (pinfunction "23_23") (pintype "bidirectional"))
      (node (ref "X2") (pin "24") (pinfunction "24_24") (pintype "bidirectional"))
      (node (ref "Z1") (pin "1") (pinfunction "A1_1") (pintype "passive"))
      (node (ref "Z2") (pin "1") (pinfunction "A1_1") (pintype "passive"))
    )
    (net (code "34") (name "INT0RX1") (class "Default")
      (node (ref "IC1") (pin "11") (pinfunction "PCINT26/INT0_PD2_11") (pintype "bidirectional"))
      (node (ref "IC11") (pin "11") (pinfunction "4Y_11") (pintype "bidirectional"))
      (node (ref "IC2") (pin "13") (pinfunction "R1OUT_13") (pintype "output"))
      (node (ref "IC4") (pin "13") (pinfunction "R1OUT_13") (pintype "output"))
      (node (ref "IC6") (pin "14") (pinfunction "1Y3_14") (pintype "bidirectional"))
      (node (ref "JP15") (pin "2") (pinfunction "2_2") (pintype "passive"))
    )
    (net (code "35") (name "INT1TX1") (class "Default")
      (node (ref "IC1") (pin "12") (pinfunction "PCINT27/INT1_PD3_12") (pintype "bidirectional"))
      (node (ref "IC11") (pin "8") (pinfunction "3Y_8") (pintype "bidirectional"))
      (node (ref "IC2") (pin "12") (pinfunction "T1IN_12") (pintype "input"))
      (node (ref "IC4") (pin "12") (pinfunction "T1IN_12") (pintype "input"))
      (node (ref "JP15") (pin "1") (pinfunction "1_1") (pintype "passive"))
      (node (ref "U2") (pin "30") (pinfunction "PD0(RXD)_30") (pintype "bidirectional"))
    )
    (net (code "36") (name "MODE") (class "Default")
      (node (ref "IC1") (pin "16") (pinfunction "PCINT31/OC2A_PD7_16") (pintype "bidirectional"))
      (node (ref "S2") (pin "3") (pinfunction "2_3") (pintype "passive"))
    )
    (net (code "37") (name "MOSI") (class "Default")
      (node (ref "IC1") (pin "1") (pinfunction "PCINT13/MOSI_PB5_1") (pintype "bidirectional"))
      (node (ref "IC5") (pin "2") (pinfunction "SDI_2") (pintype "bidirectional"))
      (node (ref "J1") (pin "4") (pinfunction "4_4") (pintype "passive"))
    )
    (net (code "38") (name "MUX_IN0") (class "Default")
      (node (ref "R20") (pin "2") (pinfunction "2_2") (pintype "passive"))
      (node (ref "R21") (pin "2") (pinfunction "2_2") (pintype "passive"))
      (node (ref "R22") (pin "1") (pinfunction "1_1") (pintype "passive"))
      (node (ref "U1") (pin "4") (pinfunction "4_4") (pintype "bidirectional"))
    )
    (net (code "39") (name "MUX_OUT") (class "Default")
      (node (ref "R15") (pin "1") (pinfunction "1_1") (pintype "passive"))
      (node (ref "U1") (pin "8") (pinfunction "8_8") (pintype "bidirectional"))
    )
    (net (code "40") (name "Net-(IC1-XTAL1)") (class "Default")
      (node (ref "C6") (pin "2") (pinfunction "2_2") (pintype "passive"))
      (node (ref "IC1") (pin "8") (pinfunction "XTAL1_8") (pintype "input"))
      (node (ref "Y1") (pin "P$1") (pinfunction "P$1_P$1") (pintype "passive"))
    )
    (net (code "41") (name "Net-(IC1-XTAL2)") (class "Default")
      (node (ref "C5") (pin "2") (pinfunction "2_2") (pintype "passive"))
      (node (ref "IC1") (pin "7") (pinfunction "XTAL2_7") (pintype "output"))
      (node (ref "Y1") (pin "P$2") (pinfunction "P$2_P$2") (pintype "passive"))
    )
    (net (code "42") (name "Net-(IC2-C1+)") (class "Default")
      (node (ref "C1") (pin "1") (pinfunction "1_1") (pintype "passive"))
      (node (ref "IC2") (pin "2") (pinfunction "C1+_2") (pintype "passive"))
    )
    (net (code "43") (name "Net-(IC2-C1-)") (class "Default")
      (node (ref "C1") (pin "2") (pinfunction "2_2") (pintype "passive"))
      (node (ref "IC2") (pin "4") (pinfunction "C1-_4") (pintype "passive"))
    )
    (net (code "44") (name "Net-(IC2-C2+)") (class "Default")
      (node (ref "C2") (pin "1") (pinfunction "1_1") (pintype "passive"))
      (node (ref "IC2") (pin "5") (pinfunction "C2+_5") (pintype "passive"))
    )
    (net (code "45") (name "Net-(IC2-C2-)") (class "Default")
      (node (ref "C2") (pin "2") (pinfunction "2_2") (pintype "passive"))
      (node (ref "IC2") (pin "6") (pinfunction "C2-_6") (pintype "passive"))
    )
    (net (code "46") (name "Net-(IC2-V+)") (class "Default")
      (node (ref "C3") (pin "2") (pinfunction "2_2") (pintype "passive"))
      (node (ref "IC2") (pin "3") (pinfunction "V+_3") (pintype "power_in"))
    )
    (net (code "47") (name "Net-(IC2-V-)") (class "Default")
      (node (ref "C4") (pin "1") (pinfunction "1_1") (pintype "passive"))
      (node (ref "IC2") (pin "7") (pinfunction "V-_7") (pintype "power_in"))
    )
    (net (code "48") (name "Net-(IC3-RSET)") (class "Default")
      (node (ref "C8") (pin "2") (pinfunction "2_2") (pintype "passive"))
      (node (ref "IC3") (pin "P6") (pinfunction "RSET_P6") (pintype "power_in"))
      (node (ref "R1") (pin "1") (pinfunction "1_1") (pintype "passive"))
    )
    (net (code "49") (name "Net-(IC3-VID_IN)") (class "Default")
      (node (ref "C9") (pin "2") (pinfunction "2_2") (pintype "passive"))
      (node (ref "IC3") (pin "P2") (pinfunction "VID_IN_P2") (pintype "input"))
    )
    (net (code "50") (name "Net-(IC4-C1+)") (class "Default")
      (node (ref "C16") (pin "1") (pinfunction "1_1") (pintype "passive"))
      (node (ref "IC4") (pin "2") (pinfunction "C1+_2") (pintype "passive"))
    )
    (net (code "51") (name "Net-(IC4-C1-)") (class "Default")
      (node (ref "C16") (pin "2") (pinfunction "2_2") (pintype "passive"))
      (node (ref "IC4") (pin "4") (pinfunction "C1-_4") (pintype "passive"))
    )
    (net (code "52") (name "Net-(IC4-C2+)") (class "Default")
      (node (ref "C17") (pin "1") (pinfunction "1_1") (pintype "passive"))
      (node (ref "IC4") (pin "5") (pinfunction "C2+_5") (pintype "passive"))
    )
    (net (code "53") (name "Net-(IC4-C2-)") (class "Default")
      (node (ref "C17") (pin "2") (pinfunction "2_2") (pintype "passive"))
      (node (ref "IC4") (pin "6") (pinfunction "C2-_6") (pintype "passive"))
    )
    (net (code "54") (name "Net-(IC4-V+)") (class "Default")
      (node (ref "C18") (pin "2") (pinfunction "2_2") (pintype "passive"))
      (node (ref "IC4") (pin "3") (pinfunction "V+_3") (pintype "power_in"))
    )
    (net (code "55") (name "Net-(IC4-V-)") (class "Default")
      (node (ref "C19") (pin "1") (pinfunction "1_1") (pintype "passive"))
      (node (ref "IC4") (pin "7") (pinfunction "V-_7") (pintype "power_in"))
    )
    (net (code "56") (name "Net-(IC5-O0)") (class "Default")
      (node (ref "IC5") (pin "5") (pinfunction "O0_5") (pintype "bidirectional"))
      (node (ref "LED3") (pin "C") (pinfunction "C_C") (pintype "passive"))
    )
    (net (code "57") (name "Net-(IC5-O1)") (class "Default")
      (node (ref "IC5") (pin "6") (pinfunction "O1_6") (pintype "bidirectional"))
      (node (ref "LED13") (pin "C") (pinfunction "C_C") (pintype "passive"))
    )
    (net (code "58") (name "Net-(IC5-O2)") (class "Default")
      (node (ref "IC5") (pin "7") (pinfunction "O2_7") (pintype "bidirectional"))
      (node (ref "LED14") (pin "C") (pinfunction "C_C") (pintype "passive"))
    )
    (net (code "59") (name "Net-(IC5-O3)") (class "Default")
      (node (ref "IC5") (pin "8") (pinfunction "O3_8") (pintype "bidirectional"))
      (node (ref "LED15") (pin "C") (pinfunction "C_C") (pintype "passive"))
    )
    (net (code "60") (name "Net-(IC5-O4)") (class "Default")
      (node (ref "IC5") (pin "9") (pinfunction "O4_9") (pintype "bidirectional"))
      (node (ref "LED16") (pin "C") (pinfunction "C_C") (pintype "passive"))
    )
    (net (code "61") (name "Net-(IC5-O5)") (class "Default")
      (node (ref "IC5") (pin "10") (pinfunction "O5_10") (pintype "bidirectional"))
      (node (ref "LED17") (pin "C") (pinfunction "C_C") (pintype "passive"))
    )
    (net (code "62") (name "Net-(IC5-O6)") (class "Default")
      (node (ref "IC5") (pin "11") (pinfunction "O6_11") (pintype "bidirectional"))
      (node (ref "LED18") (pin "C") (pinfunction "C_C") (pintype "passive"))
    )
    (net (code "63") (name "Net-(IC5-O7)") (class "Default")
      (node (ref "IC5") (pin "12") (pinfunction "O7_12") (pintype "bidirectional"))
      (node (ref "LED19") (pin "C") (pinfunction "C_C") (pintype "passive"))
    )
    (net (code "64") (name "Net-(IC5-O10)") (class "Default")
      (node (ref "IC5") (pin "15") (pinfunction "O10_15") (pintype "bidirectional"))
      (node (ref "LED6") (pin "C") (pinfunction "C_C") (pintype "passive"))
    )
    (net (code "65") (name "Net-(IC5-O11)") (class "Default")
      (node (ref "IC5") (pin "16") (pinfunction "O11_16") (pintype "bidirectional"))
      (node (ref "LED7") (pin "C") (pinfunction "C_C") (pintype "passive"))
    )
    (net (code "66") (name "Net-(IC5-O12)") (class "Default")
      (node (ref "IC5") (pin "17") (pinfunction "O12_17") (pintype "bidirectional"))
      (node (ref "LED8") (pin "C") (pinfunction "C_C") (pintype "passive"))
    )
    (net (code "67") (name "Net-(IC5-O14)") (class "Default")
      (node (ref "IC5") (pin "19") (pinfunction "O14_19") (pintype "bidirectional"))
      (node (ref "LED10") (pin "C") (pinfunction "C_C") (pintype "passive"))
    )
    (net (code "68") (name "Net-(IC5-O15)") (class "Default")
      (node (ref "IC5") (pin "20") (pinfunction "O15_20") (pintype "bidirectional"))
      (node (ref "LED11") (pin "C") (pinfunction "C_C") (pintype "passive"))
    )
    (net (code "69") (name "Net-(IC5-R-EXT)") (class "Default")
      (node (ref "IC5") (pin "23") (pinfunction "R-EXT_23") (pintype "bidirectional"))
      (node (ref "R11") (pin "1") (pinfunction "1_1") (pintype "passive"))
    )
    (net (code "70") (name "Net-(IC8-V)") (class "Default")
      (node (ref "IC8") (pin "1") (pinfunction "V_1") (pintype "bidirectional"))
      (node (ref "R16") (pin "2") (pinfunction "2_2") (pintype "passive"))
    )
    (net (code "71") (name "Net-(J3-OUT)") (class "Default")
      (node (ref "J3") (pin "S") (pinfunction "OUT_S") (pintype "bidirectional"))
      (node (ref "JP9") (pin "1") (pinfunction "1_1") (pintype "passive"))
      (node (ref "R15") (pin "2") (pinfunction "2_2") (pintype "passive"))
    )
    (net (code "72") (name "Net-(J4-Pad1)") (class "Default")
      (node (ref "J4") (pin "1") (pinfunction "1_1") (pintype "bidirectional"))
      (node (ref "SJ1") (pin "1") (pinfunction "1_1") (pintype "passive"))
    )
    (net (code "73") (name "Net-(J4-Pad2)") (class "Default")
      (node (ref "J4") (pin "2") (pinfunction "2_2") (pintype "bidirectional"))
      (node (ref "R24") (pin "1") (pinfunction "1_1") (pintype "passive"))
      (node (ref "R25") (pin "2") (pinfunction "2_2") (pintype "passive"))
    )
    (net (code "74") (name "Net-(J4-Pad3)") (class "Default")
      (node (ref "J4") (pin "3") (pinfunction "3_3") (pintype "bidirectional"))
      (node (ref "R13") (pin "1") (pinfunction "1_1") (pintype "passive"))
      (node (ref "R23") (pin "2") (pinfunction "2_2") (pintype "passive"))
    )
    (net (code "75") (name "Net-(J5-Pad1)") (class "Default")
      (node (ref "J5") (pin "1") (pinfunction "1_1") (pintype "bidirectional"))
      (node (ref "R10") (pin "1") (pinfunction "1_1") (pintype "passive"))
    )
    (net (code "76") (name "Net-(J5-Pad2)") (class "Default")
      (node (ref "J5") (pin "2") (pinfunction "2_2") (pintype "bidirectional"))
      (node (ref "R9") (pin "1") (pinfunction "1_1") (pintype "passive"))
    )
    (net (code "77") (name "Net-(LED2-PadC)") (class "Default")
      (node (ref "LED2") (pin "C") (pinfunction "C_C") (pintype "passive"))
      (node (ref "R2") (pin "2") (pinfunction "2_2") (pintype "passive"))
    )
    (net (code "78") (name "Net-(R14-Pad2)") (class "Default")
      (node (ref "R14") (pin "2") (pinfunction "2_2") (pintype "passive"))
      (node (ref "R17") (pin "1") (pinfunction "1_1") (pintype "passive"))
      (node (ref "R7") (pin "2") (pinfunction "2_2") (pintype "passive"))
    )
    (net (code "79") (name "Net-(R17-Pad2)") (class "Default")
      (node (ref "R17") (pin "2") (pinfunction "2_2") (pintype "passive"))
      (node (ref "R18") (pin "1") (pinfunction "1_1") (pintype "passive"))
      (node (ref "R3") (pin "2") (pinfunction "2_2") (pintype "passive"))
    )
    (net (code "80") (name "Net-(R18-Pad2)") (class "Default")
      (node (ref "R18") (pin "2") (pinfunction "2_2") (pintype "passive"))
      (node (ref "R19") (pin "2") (pinfunction "2_2") (pintype "passive"))
      (node (ref "R20") (pin "1") (pinfunction "1_1") (pintype "passive"))
    )
    (net (code "81") (name "Net-(U2-PB6(XTAL1{slash}TOSC1))") (class "Default")
      (node (ref "C14") (pin "2") (pinfunction "2_2") (pintype "passive"))
      (node (ref "U2") (pin "7") (pinfunction "PB6(XTAL1/TOSC1)_7") (pintype "bidirectional"))
      (node (ref "Y2") (pin "P$2") (pinfunction "P$2_P$2") (pintype "passive"))
    )
    (net (code "82") (name "Net-(U2-PB7(XTAL2{slash}TOSC2))") (class "Default")
      (node (ref "C15") (pin "1") (pinfunction "1_1") (pintype "passive"))
      (node (ref "U2") (pin "8") (pinfunction "PB7(XTAL2/TOSC2)_8") (pintype "bidirectional"))
      (node (ref "Y2") (pin "P$1") (pinfunction "P$1_P$1") (pintype "passive"))
    )
    (net (code "83") (name "PR8210A_R_I~{E}") (class "Default")
      (node (ref "IC7") (pin "P$2") (pinfunction "2_P$2") (pintype "input"))
      (node (ref "X2") (pin "9") (pinfunction "9_9") (pintype "bidirectional"))
    )
    (net (code "84") (name "RX") (class "Default")
      (node (ref "IC1") (pin "9") (pinfunction "PCINT24/RXD0_PD0_9") (pintype "bidirectional"))
      (node (ref "IC9") (pin "3") (pinfunction "1A1_3") (pintype "bidirectional"))
      (node (ref "JP8") (pin "3") (pinfunction "3_3") (pintype "passive"))
    )
    (net (code "85") (name "RX3V3") (class "Default")
      (node (ref "IC9") (pin "5") (pinfunction "1B2_5") (pintype "bidirectional"))
      (node (ref "JP7") (pin "10") (pinfunction "10_10") (pintype "passive"))
    )
    (net (code "86") (name "S2") (class "Default")
      (node (ref "IC2") (pin "14") (pinfunction "R1IN_14") (pintype "input"))
      (node (ref "IC4") (pin "15") (pinfunction "T1OUT_15") (pintype "output"))
      (node (ref "X1") (pin "P2") (pinfunction "2_P2") (pintype "bidirectional"))
    )
    (net (code "87") (name "S3") (class "Default")
      (node (ref "IC2") (pin "15") (pinfunction "T1OUT_15") (pintype "output"))
      (node (ref "IC4") (pin "14") (pinfunction "R1IN_14") (pintype "input"))
      (node (ref "X1") (pin "P3") (pinfunction "3_P3") (pintype "bidirectional"))
    )
    (net (code "88") (name "S4") (class "Default")
      (node (ref "IC2") (pin "9") (pinfunction "R2IN_9") (pintype "input"))
      (node (ref "IC4") (pin "8") (pinfunction "T2OUT_8") (pintype "output"))
      (node (ref "X1") (pin "P4") (pinfunction "4_P4") (pintype "bidirectional"))
    )
    (net (code "89") (name "S5") (class "Default")
      (node (ref "IC2") (pin "8") (pinfunction "T2OUT_8") (pintype "output"))
      (node (ref "IC4") (pin "9") (pinfunction "R2IN_9") (pintype "input"))
      (node (ref "X1") (pin "P5") (pinfunction "5_P5") (pintype "bidirectional"))
    )
    (net (code "90") (name "SCK") (class "Default")
      (node (ref "IC1") (pin "3") (pinfunction "PCINT15/SCK_PB7_3") (pintype "bidirectional"))
      (node (ref "IC5") (pin "3") (pinfunction "CLK_3") (pintype "bidirectional"))
      (node (ref "J1") (pin "3") (pinfunction "3_3") (pintype "passive"))
    )
    (net (code "91") (name "SSR") (class "Default")
      (node (ref "IC1") (pin "26") (pinfunction "PCINT23/TOSC2_PC7_26") (pintype "bidirectional"))
      (node (ref "IC10") (pin "P$6") (pinfunction "C_P$6") (pintype "bidirectional"))
      (node (ref "IC11") (pin "10") (pinfunction "3OE_10") (pintype "bidirectional"))
      (node (ref "IC11") (pin "13") (pinfunction "4OE_13") (pintype "bidirectional"))
      (node (ref "R16") (pin "1") (pinfunction "1_1") (pintype "passive"))
    )
    (net (code "92") (name "STAND_BY") (class "Default")
      (node (ref "JP11") (pin "4") (pinfunction "4_4") (pintype "passive"))
      (node (ref "U2") (pin "14") (pinfunction "PB2(SS/OC1B)_14") (pintype "bidirectional"))
      (node (ref "X2") (pin "5") (pinfunction "5_5") (pintype "bidirectional"))
    )
    (net (code "93") (name "TCK") (class "Default")
      (node (ref "IC1") (pin "21") (pinfunction "PCINT18/TCK_PC2_21") (pintype "bidirectional"))
      (node (ref "JP5") (pin "1") (pinfunction "1_1") (pintype "passive"))
    )
    (net (code "94") (name "TDI") (class "Default")
      (node (ref "IC1") (pin "24") (pinfunction "PCINT21/TDI_PC5_24") (pintype "bidirectional"))
      (node (ref "JP5") (pin "9") (pinfunction "9_9") (pintype "passive"))
    )
    (net (code "95") (name "TDO") (class "Default")
      (node (ref "IC1") (pin "23") (pinfunction "PCINT20/TDO_PC4_23") (pintype "bidirectional"))
      (node (ref "JP5") (pin "3") (pinfunction "3_3") (pintype "passive"))
    )
    (net (code "96") (name "TIED") (class "Default")
      (node (ref "IC8") (pin "3") (pinfunction "L3_3") (pintype "bidirectional"))
      (node (ref "X1") (pin "P20") (pinfunction "20_P20") (pintype "bidirectional"))
      (node (ref "X1") (pin "P6") (pinfunction "6_P6") (pintype "bidirectional"))
    )
    (net (code "97") (name "TMS") (class "Default")
      (node (ref "IC1") (pin "22") (pinfunction "PCINT19/TMS_PC3_22") (pintype "bidirectional"))
      (node (ref "JP5") (pin "5") (pinfunction "5_5") (pintype "passive"))
    )
    (net (code "98") (name "TX") (class "Default")
      (node (ref "IC1") (pin "10") (pinfunction "PCINT25/TXD0_PD1_10") (pintype "bidirectional"))
      (node (ref "IC9") (pin "4") (pinfunction "1A2_4") (pintype "bidirectional"))
      (node (ref "JP8") (pin "4") (pinfunction "4_4") (pintype "passive"))
    )
    (net (code "99") (name "TX3V3") (class "Default")
      (node (ref "IC9") (pin "2") (pinfunction "1B1_2") (pintype "bidirectional"))
      (node (ref "JP7") (pin "8") (pinfunction "8_8") (pintype "passive"))
    )
    (net (code "100") (name "VCC") (class "Default")
      (node (ref "C10") (pin "1") (pinfunction "1_1") (pintype "passive"))
      (node (ref "C11") (pin "1") (pinfunction "+_1") (pintype "passive"))
      (node (ref "C12") (pin "2") (pinfunction "2_2") (pintype "passive"))
      (node (ref "C13") (pin "1") (pinfunction "1_1") (pintype "passive"))
      (node (ref "C18") (pin "1") (pinfunction "1_1") (pintype "passive"))
      (node (ref "C20") (pin "2") (pinfunction "2_2") (pintype "passive"))
      (node (ref "C21") (pin "1") (pinfunction "1_1") (pintype "passive"))
      (node (ref "C22") (pin "1") (pinfunction "1_1") (pintype "passive"))
      (node (ref "C23") (pin "1") (pinfunction "1_1") (pintype "passive"))
      (node (ref "C24") (pin "1") (pinfunction "1_1") (pintype "passive"))
      (node (ref "C25") (pin "1") (pinfunction "1_1") (pintype "passive"))
      (node (ref "C26") (pin "1") (pinfunction "1_1") (pintype "passive"))
      (node (ref "C27") (pin "1") (pinfunction "1_1") (pintype "passive"))
      (node (ref "C3") (pin "1") (pinfunction "1_1") (pintype "passive"))
      (node (ref "C7") (pin "1") (pinfunction "1_1") (pintype "passive"))
      (node (ref "F1") (pin "P$2") (pinfunction "2_P$2") (pintype "bidirectional"))
      (node (ref "IC1") (pin "17") (pinfunction "VCC_17") (pintype "power_in"))
      (node (ref "IC1") (pin "27") (pinfunction "AVCC_27") (pintype "power_in"))
      (node (ref "IC1") (pin "38") (pinfunction "VCC_38") (pintype "power_in"))
      (node (ref "IC1") (pin "5") (pinfunction "VCC_5") (pintype "power_in"))
      (node (ref "IC10") (pin "P$5") (pinfunction "V_P$5") (pintype "bidirectional"))
      (node (ref "IC11") (pin "14") (pinfunction "VCC_14") (pintype "bidirectional"))
      (node (ref "IC2") (pin "17") (pinfunction "VCC_17") (pintype "power_in"))
      (node (ref "IC3") (pin "P8") (pinfunction "VCC_P8") (pintype "power_in"))
      (node (ref "IC4") (pin "17") (pinfunction "VCC_17") (pintype "power_in"))
      (node (ref "IC5") (pin "24") (pinfunction "VDD_24") (pintype "bidirectional"))
      (node (ref "IC5") (pin "4") (pinfunction "LE_4") (pintype "bidirectional"))
      (node (ref "IC6") (pin "20") (pinfunction "VCC_20") (pintype "bidirectional"))
      (node (ref "IC7") (pin "P$5") (pinfunction "VCC_5_P$5") (pintype "bidirectional"))
      (node (ref "IC9") (pin "13") (pinfunction "2OE'_13") (pintype "bidirectional"))
      (node (ref "IC9") (pin "24") (pinfunction "VCC_24") (pintype "bidirectional"))
      (node (ref "IR1") (pin "2") (pinfunction "VCC2_2") (pintype "bidirectional"))
      (node (ref "J1") (pin "2") (pinfunction "2_2") (pintype "passive"))
      (node (ref "J8") (pin "2") (pinfunction "2_2") (pintype "passive"))
      (node (ref "JP16") (pin "1") (pinfunction "S_1") (pintype "passive"))
      (node (ref "JP17") (pin "1") (pinfunction "S_1") (pintype "passive"))
      (node (ref "JP5") (pin "4") (pinfunction "4_4") (pintype "passive"))
      (node (ref "JP8") (pin "2") (pinfunction "2_2") (pintype "passive"))
      (node (ref "LED10") (pin "A") (pinfunction "A_A") (pintype "passive"))
      (node (ref "LED11") (pin "A") (pinfunction "A_A") (pintype "passive"))
      (node (ref "LED13") (pin "A") (pinfunction "A_A") (pintype "passive"))
      (node (ref "LED14") (pin "A") (pinfunction "A_A") (pintype "passive"))
      (node (ref "LED15") (pin "A") (pinfunction "A_A") (pintype "passive"))
      (node (ref "LED16") (pin "A") (pinfunction "A_A") (pintype "passive"))
      (node (ref "LED17") (pin "A") (pinfunction "A_A") (pintype "passive"))
      (node (ref "LED18") (pin "A") (pinfunction "A_A") (pintype "passive"))
      (node (ref "LED19") (pin "A") (pinfunction "A_A") (pintype "passive"))
      (node (ref "LED2") (pin "A") (pinfunction "A_A") (pintype "passive"))
      (node (ref "LED3") (pin "A") (pinfunction "A_A") (pintype "passive"))
      (node (ref "LED6") (pin "A") (pinfunction "A_A") (pintype "passive"))
      (node (ref "LED7") (pin "A") (pinfunction "A_A") (pintype "passive"))
      (node (ref "LED8") (pin "A") (pinfunction "A_A") (pintype "passive"))
      (node (ref "R12") (pin "2") (pinfunction "2_2") (pintype "passive"))
      (node (ref "R26") (pin "1") (pinfunction "1_1") (pintype "passive"))
      (node (ref "R27") (pin "2") (pinfunction "2_2") (pintype "passive"))
      (node (ref "R8") (pin "1") (pinfunction "1_1") (pintype "passive"))
      (node (ref "U1") (pin "3") (pinfunction "3_3") (pintype "bidirectional"))
      (node (ref "U2") (pin "18") (pinfunction "AVCC_18") (pintype "bidirectional"))
      (node (ref "U2") (pin "4") (pinfunction "VCC_4") (pintype "bidirectional"))
      (node (ref "U2") (pin "6") (pinfunction "VCC_6") (pintype "bidirectional"))
      (node (ref "Z1") (pin "2") (pinfunction "C2_2") (pintype "passive"))
      (node (ref "Z2") (pin "2") (pinfunction "C2_2") (pintype "passive"))
    )
    (net (code "101") (name "VID_IN") (class "Default")
      (node (ref "C9") (pin "1") (pinfunction "1_1") (pintype "passive"))
      (node (ref "JP10") (pin "1") (pinfunction "1_1") (pintype "passive"))
      (node (ref "R6") (pin "1") (pinfunction "1_1") (pintype "passive"))
      (node (ref "SJ1") (pin "2") (pinfunction "2_2") (pintype "passive"))
      (node (ref "U1") (pin "5") (pinfunction "5_5") (pintype "bidirectional"))
      (node (ref "VID_IN") (pin "P2") (pinfunction "2_P2") (pintype "bidirectional"))
    )
    (net (code "102") (name "VSYNC") (class "Default")
      (node (ref "IC3") (pin "P3") (pinfunction "VSYNC_P3") (pintype "output"))
      (node (ref "JP13") (pin "1") (pinfunction "1_1") (pintype "passive"))
    )
    (net (code "103") (name "unconnected-(AUD_LEFT-3-PadP3)") (class "Default")
      (node (ref "AUD_LEFT") (pin "P3") (pinfunction "3_P3") (pintype "bidirectional"))
    )
    (net (code "104") (name "unconnected-(AUD_RIGHT-3-PadP3)") (class "Default")
      (node (ref "AUD_RIGHT") (pin "P3") (pinfunction "3_P3") (pintype "bidirectional"))
    )
    (net (code "105") (name "unconnected-(IC1-AREF-Pad29)") (class "Default")
      (node (ref "IC1") (pin "29") (pinfunction "AREF_29") (pintype "passive"))
    )
    (net (code "106") (name "unconnected-(IC1-PCINT12{slash}OC0B{slash}SS_PB4-Pad44)") (class "Default")
      (node (ref "IC1") (pin "44") (pinfunction "PCINT12/OC0B/SS_PB4_44") (pintype "bidirectional"))
    )
    (net (code "107") (name "unconnected-(IC3-BURST-PadP5)") (class "Default")
      (node (ref "IC3") (pin "P5") (pinfunction "BURST_P5") (pintype "output"))
    )
    (net (code "108") (name "unconnected-(IC5-O8-Pad13)") (class "Default")
      (node (ref "IC5") (pin "13") (pinfunction "O8_13") (pintype "bidirectional"))
    )
    (net (code "109") (name "unconnected-(IC5-O9-Pad14)") (class "Default")
      (node (ref "IC5") (pin "14") (pinfunction "O9_14") (pintype "bidirectional"))
    )
    (net (code "110") (name "unconnected-(IC5-O13-Pad18)") (class "Default")
      (node (ref "IC5") (pin "18") (pinfunction "O13_18") (pintype "bidirectional"))
    )
    (net (code "111") (name "unconnected-(IC5-SD0-Pad22)") (class "Default")
      (node (ref "IC5") (pin "22") (pinfunction "SD0_22") (pintype "bidirectional"))
    )
    (net (code "112") (name "unconnected-(IC6-1A1-Pad2)") (class "Default")
      (node (ref "IC6") (pin "2") (pinfunction "1A1_2") (pintype "bidirectional"))
    )
    (net (code "113") (name "unconnected-(IC6-1A2-Pad4)") (class "Default")
      (node (ref "IC6") (pin "4") (pinfunction "1A2_4") (pintype "bidirectional"))
    )
    (net (code "114") (name "unconnected-(IC6-1A4-Pad8)") (class "Default")
      (node (ref "IC6") (pin "8") (pinfunction "1A4_8") (pintype "bidirectional"))
    )
    (net (code "115") (name "unconnected-(IC6-1Y1-Pad18)") (class "Default")
      (node (ref "IC6") (pin "18") (pinfunction "1Y1_18") (pintype "bidirectional"))
    )
    (net (code "116") (name "unconnected-(IC6-1Y2-Pad16)") (class "Default")
      (node (ref "IC6") (pin "16") (pinfunction "1Y2_16") (pintype "bidirectional"))
    )
    (net (code "117") (name "unconnected-(IC6-1Y4-Pad12)") (class "Default")
      (node (ref "IC6") (pin "12") (pinfunction "1Y4_12") (pintype "bidirectional"))
    )
    (net (code "118") (name "unconnected-(IC6-2A2-Pad13)") (class "Default")
      (node (ref "IC6") (pin "13") (pinfunction "2A2_13") (pintype "bidirectional"))
    )
    (net (code "119") (name "unconnected-(IC6-2Y2-Pad7)") (class "Default")
      (node (ref "IC6") (pin "7") (pinfunction "2Y2_7") (pintype "bidirectional"))
    )
    (net (code "120") (name "unconnected-(IC9-1A5-Pad11)") (class "Default")
      (node (ref "IC9") (pin "11") (pinfunction "1A5_11") (pintype "bidirectional"))
    )
    (net (code "121") (name "unconnected-(IC9-1B5-Pad10)") (class "Default")
      (node (ref "IC9") (pin "10") (pinfunction "1B5_10") (pintype "bidirectional"))
    )
    (net (code "122") (name "unconnected-(IC9-2A1-Pad14)") (class "Default")
      (node (ref "IC9") (pin "14") (pinfunction "2A1_14") (pintype "bidirectional"))
    )
    (net (code "123") (name "unconnected-(IC9-2A2-Pad17)") (class "Default")
      (node (ref "IC9") (pin "17") (pinfunction "2A2_17") (pintype "bidirectional"))
    )
    (net (code "124") (name "unconnected-(IC9-2A3-Pad18)") (class "Default")
      (node (ref "IC9") (pin "18") (pinfunction "2A3_18") (pintype "bidirectional"))
    )
    (net (code "125") (name "unconnected-(IC9-2A4-Pad21)") (class "Default")
      (node (ref "IC9") (pin "21") (pinfunction "2A4_21") (pintype "bidirectional"))
    )
    (net (code "126") (name "unconnected-(IC9-2A5-Pad22)") (class "Default")
      (node (ref "IC9") (pin "22") (pinfunction "2A5_22") (pintype "bidirectional"))
    )
    (net (code "127") (name "unconnected-(IC9-2B1-Pad15)") (class "Default")
      (node (ref "IC9") (pin "15") (pinfunction "2B1_15") (pintype "bidirectional"))
    )
    (net (code "128") (name "unconnected-(IC9-2B2-Pad16)") (class "Default")
      (node (ref "IC9") (pin "16") (pinfunction "2B2_16") (pintype "bidirectional"))
    )
    (net (code "129") (name "unconnected-(IC9-2B3-Pad19)") (class "Default")
      (node (ref "IC9") (pin "19") (pinfunction "2B3_19") (pintype "bidirectional"))
    )
    (net (code "130") (name "unconnected-(IC9-2B4-Pad20)") (class "Default")
      (node (ref "IC9") (pin "20") (pinfunction "2B4_20") (pintype "bidirectional"))
    )
    (net (code "131") (name "unconnected-(IC9-2B5-Pad23)") (class "Default")
      (node (ref "IC9") (pin "23") (pinfunction "2B5_23") (pintype "bidirectional"))
    )
    (net (code "132") (name "unconnected-(IC11-2A-Pad5)") (class "Default")
      (node (ref "IC11") (pin "5") (pinfunction "2A_5") (pintype "bidirectional"))
    )
    (net (code "133") (name "unconnected-(IC11-2Y-Pad6)") (class "Default")
      (node (ref "IC11") (pin "6") (pinfunction "2Y_6") (pintype "bidirectional"))
    )
    (net (code "134") (name "unconnected-(J5-Pad3)") (class "Default")
      (node (ref "J5") (pin "3") (pinfunction "3_3") (pintype "bidirectional"))
    )
    (net (code "135") (name "unconnected-(JP5-Pad7)") (class "Default")
      (node (ref "JP5") (pin "7") (pinfunction "7_7") (pintype "passive"))
    )
    (net (code "136") (name "unconnected-(JP5-Pad8)") (class "Default")
      (node (ref "JP5") (pin "8") (pinfunction "8_8") (pintype "passive"))
    )
    (net (code "137") (name "unconnected-(JP7-Pad1)") (class "Default")
      (node (ref "JP7") (pin "1") (pinfunction "1_1") (pintype "passive"))
    )
    (net (code "138") (name "unconnected-(JP7-Pad3)") (class "Default")
      (node (ref "JP7") (pin "3") (pinfunction "3_3") (pintype "passive"))
    )
    (net (code "139") (name "unconnected-(JP7-Pad5)") (class "Default")
      (node (ref "JP7") (pin "5") (pinfunction "5_5") (pintype "passive"))
    )
    (net (code "140") (name "unconnected-(JP7-Pad7)") (class "Default")
      (node (ref "JP7") (pin "7") (pinfunction "7_7") (pintype "passive"))
    )
    (net (code "141") (name "unconnected-(JP7-Pad11)") (class "Default")
      (node (ref "JP7") (pin "11") (pinfunction "11_11") (pintype "passive"))
    )
    (net (code "142") (name "unconnected-(JP7-Pad12)") (class "Default")
      (node (ref "JP7") (pin "12") (pinfunction "12_12") (pintype "passive"))
    )
    (net (code "143") (name "unconnected-(JP7-Pad13)") (class "Default")
      (node (ref "JP7") (pin "13") (pinfunction "13_13") (pintype "passive"))
    )
    (net (code "144") (name "unconnected-(JP7-Pad15)") (class "Default")
      (node (ref "JP7") (pin "15") (pinfunction "15_15") (pintype "passive"))
    )
    (net (code "145") (name "unconnected-(JP7-Pad17)") (class "Default")
      (node (ref "JP7") (pin "17") (pinfunction "17_17") (pintype "passive"))
    )
    (net (code "146") (name "unconnected-(JP7-Pad19)") (class "Default")
      (node (ref "JP7") (pin "19") (pinfunction "19_19") (pintype "passive"))
    )
    (net (code "147") (name "unconnected-(JP7-Pad21)") (class "Default")
      (node (ref "JP7") (pin "21") (pinfunction "21_21") (pintype "passive"))
    )
    (net (code "148") (name "unconnected-(JP7-Pad22)") (class "Default")
      (node (ref "JP7") (pin "22") (pinfunction "22_22") (pintype "passive"))
    )
    (net (code "149") (name "unconnected-(JP7-Pad23)") (class "Default")
      (node (ref "JP7") (pin "23") (pinfunction "23_23") (pintype "passive"))
    )
    (net (code "150") (name "unconnected-(JP7-Pad24)") (class "Default")
      (node (ref "JP7") (pin "24") (pinfunction "24_24") (pintype "passive"))
    )
    (net (code "151") (name "unconnected-(JP7-Pad26)") (class "Default")
      (node (ref "JP7") (pin "26") (pinfunction "26_26") (pintype "passive"))
    )
    (net (code "152") (name "unconnected-(U2-ADC6-Pad19)") (class "Default")
      (node (ref "U2") (pin "19") (pinfunction "ADC6_19") (pintype "bidirectional"))
    )
    (net (code "153") (name "unconnected-(U2-ADC7-Pad22)") (class "Default")
      (node (ref "U2") (pin "22") (pinfunction "ADC7_22") (pintype "bidirectional"))
    )
    (net (code "154") (name "unconnected-(U2-AREF-Pad20)") (class "Default")
      (node (ref "U2") (pin "20") (pinfunction "AREF_20") (pintype "bidirectional"))
    )
    (net (code "155") (name "unconnected-(VID_IN-3-PadP3)") (class "Default")
      (node (ref "VID_IN") (pin "P3") (pinfunction "3_P3") (pintype "bidirectional"))
    )
    (net (code "156") (name "unconnected-(X1-8-PadP8)") (class "Default")
      (node (ref "X1") (pin "P8") (pinfunction "8_P8") (pintype "bidirectional"))
    )
    (net (code "157") (name "unconnected-(X1-25-PadP25)") (class "Default")
      (node (ref "X1") (pin "P25") (pinfunction "25_P25") (pintype "bidirectional"))
    )
    (net (code "158") (name "unconnected-(X2-Pad8)") (class "Default")
      (node (ref "X2") (pin "8") (pinfunction "8_8") (pintype "bidirectional"))
    )
    (net (code "159") (name "~{AUX_MOSI_SHDN}") (class "Default")
      (node (ref "J8") (pin "4") (pinfunction "4_4") (pintype "passive"))
      (node (ref "U1") (pin "2") (pinfunction "2_2") (pintype "bidirectional"))
      (node (ref "U2") (pin "15") (pinfunction "PB3(MOSI/OC2)_15") (pintype "bidirectional"))
    )
    (net (code "160") (name "~{AUX_VSYNC}") (class "Default")
      (node (ref "IC6") (pin "17") (pinfunction "2A4_17") (pintype "bidirectional"))
      (node (ref "JP11") (pin "3") (pinfunction "3_3") (pintype "passive"))
      (node (ref "U2") (pin "12") (pinfunction "PB0(ICP)_12") (pintype "bidirectional"))
    )
    (net (code "161") (name "~{ENABLE_TX}") (class "Default")
      (node (ref "IC10") (pin "P$4") (pinfunction "Y_P$4") (pintype "bidirectional"))
      (node (ref "IC6") (pin "1") (pinfunction "1~{G}_1") (pintype "bidirectional"))
    )
    (net (code "162") (name "~{PR8210A_CMB}") (class "Default")
      (node (ref "IC6") (pin "11") (pinfunction "2A1_11") (pintype "bidirectional"))
      (node (ref "IC7") (pin "P$4") (pinfunction "4_P$4") (pintype "output"))
    )
    (net (code "163") (name "~{PR8210A_ENABLE}") (class "Default")
      (node (ref "IC1") (pin "15") (pinfunction "PCINT30/OC2B/ICP_PD6_15") (pintype "bidirectional"))
      (node (ref "IC11") (pin "1") (pinfunction "1OE_1") (pintype "bidirectional"))
      (node (ref "IC6") (pin "19") (pinfunction "2~{G}_19") (pintype "bidirectional"))
      (node (ref "R26") (pin "2") (pinfunction "2_2") (pintype "passive"))
    )
    (net (code "164") (name "~{PR8210A_R_CTRL}") (class "Default")
      (node (ref "IC7") (pin "P$1") (pinfunction "1_P$1") (pintype "input"))
      (node (ref "X2") (pin "10") (pinfunction "10_10") (pintype "bidirectional"))
    )
    (net (code "165") (name "~{PR8210_IR}") (class "Default")
      (node (ref "IR1") (pin "1") (pinfunction "OUT1_1") (pintype "bidirectional"))
      (node (ref "J5") (pin "4") (pinfunction "4_4") (pintype "bidirectional"))
    )
    (net (code "166") (name "~{PR8210_R_CTRL}") (class "Default")
      (node (ref "IC11") (pin "2") (pinfunction "1A_2") (pintype "bidirectional"))
      (node (ref "R12") (pin "1") (pinfunction "1_1") (pintype "passive"))
      (node (ref "R9") (pin "2") (pinfunction "2_2") (pintype "passive"))
      (node (ref "Z1") (pin "3") (pinfunction "C1A2_3") (pintype "passive"))
    )
    (net (code "167") (name "~{RDEN}") (class "Default")
      (node (ref "IC11") (pin "12") (pinfunction "4A_12") (pintype "bidirectional"))
      (node (ref "X1") (pin "P10") (pinfunction "10_P10") (pintype "bidirectional"))
    )
    (net (code "168") (name "~{REMOTE_CTRL}") (class "Default")
      (node (ref "IC1") (pin "25") (pinfunction "PCINT22/TOSC1_PC6_25") (pintype "bidirectional"))
      (node (ref "IC11") (pin "3") (pinfunction "1Y_3") (pintype "bidirectional"))
      (node (ref "IC6") (pin "9") (pinfunction "2Y1_9") (pintype "bidirectional"))
    )
    (net (code "169") (name "~{RST3V3}") (class "Default")
      (node (ref "IC9") (pin "6") (pinfunction "1B3_6") (pintype "bidirectional"))
      (node (ref "JP7") (pin "16") (pinfunction "16_16") (pintype "passive"))
    )
    (net (code "170") (name "~{RST}") (class "Default")
      (node (ref "IC1") (pin "4") (pinfunction "~{RESET}_4") (pintype "input"))
      (node (ref "IC9") (pin "7") (pinfunction "1A3_7") (pintype "bidirectional"))
      (node (ref "J1") (pin "5") (pinfunction "5_5") (pintype "passive"))
      (node (ref "J8") (pin "5") (pinfunction "5_5") (pintype "passive"))
      (node (ref "JP5") (pin "6") (pinfunction "6_6") (pintype "passive"))
      (node (ref "JP8") (pin "5") (pinfunction "5_5") (pintype "passive"))
      (node (ref "R8") (pin "2") (pinfunction "2_2") (pintype "passive"))
      (node (ref "S4") (pin "3") (pinfunction "2_3") (pintype "passive"))
      (node (ref "U2") (pin "29") (pinfunction "PC6(/RESET)_29") (pintype "bidirectional"))
    )
    (net (code "171") (name "~{WREN}") (class "Default")
      (node (ref "IC11") (pin "9") (pinfunction "3A_9") (pintype "bidirectional"))
      (node (ref "X1") (pin "P22") (pinfunction "22_P22") (pintype "bidirectional"))
    )
  )
)
